# Pop-Up_5_1.net
KiCad netlist of a schematic drawn in EAGLE
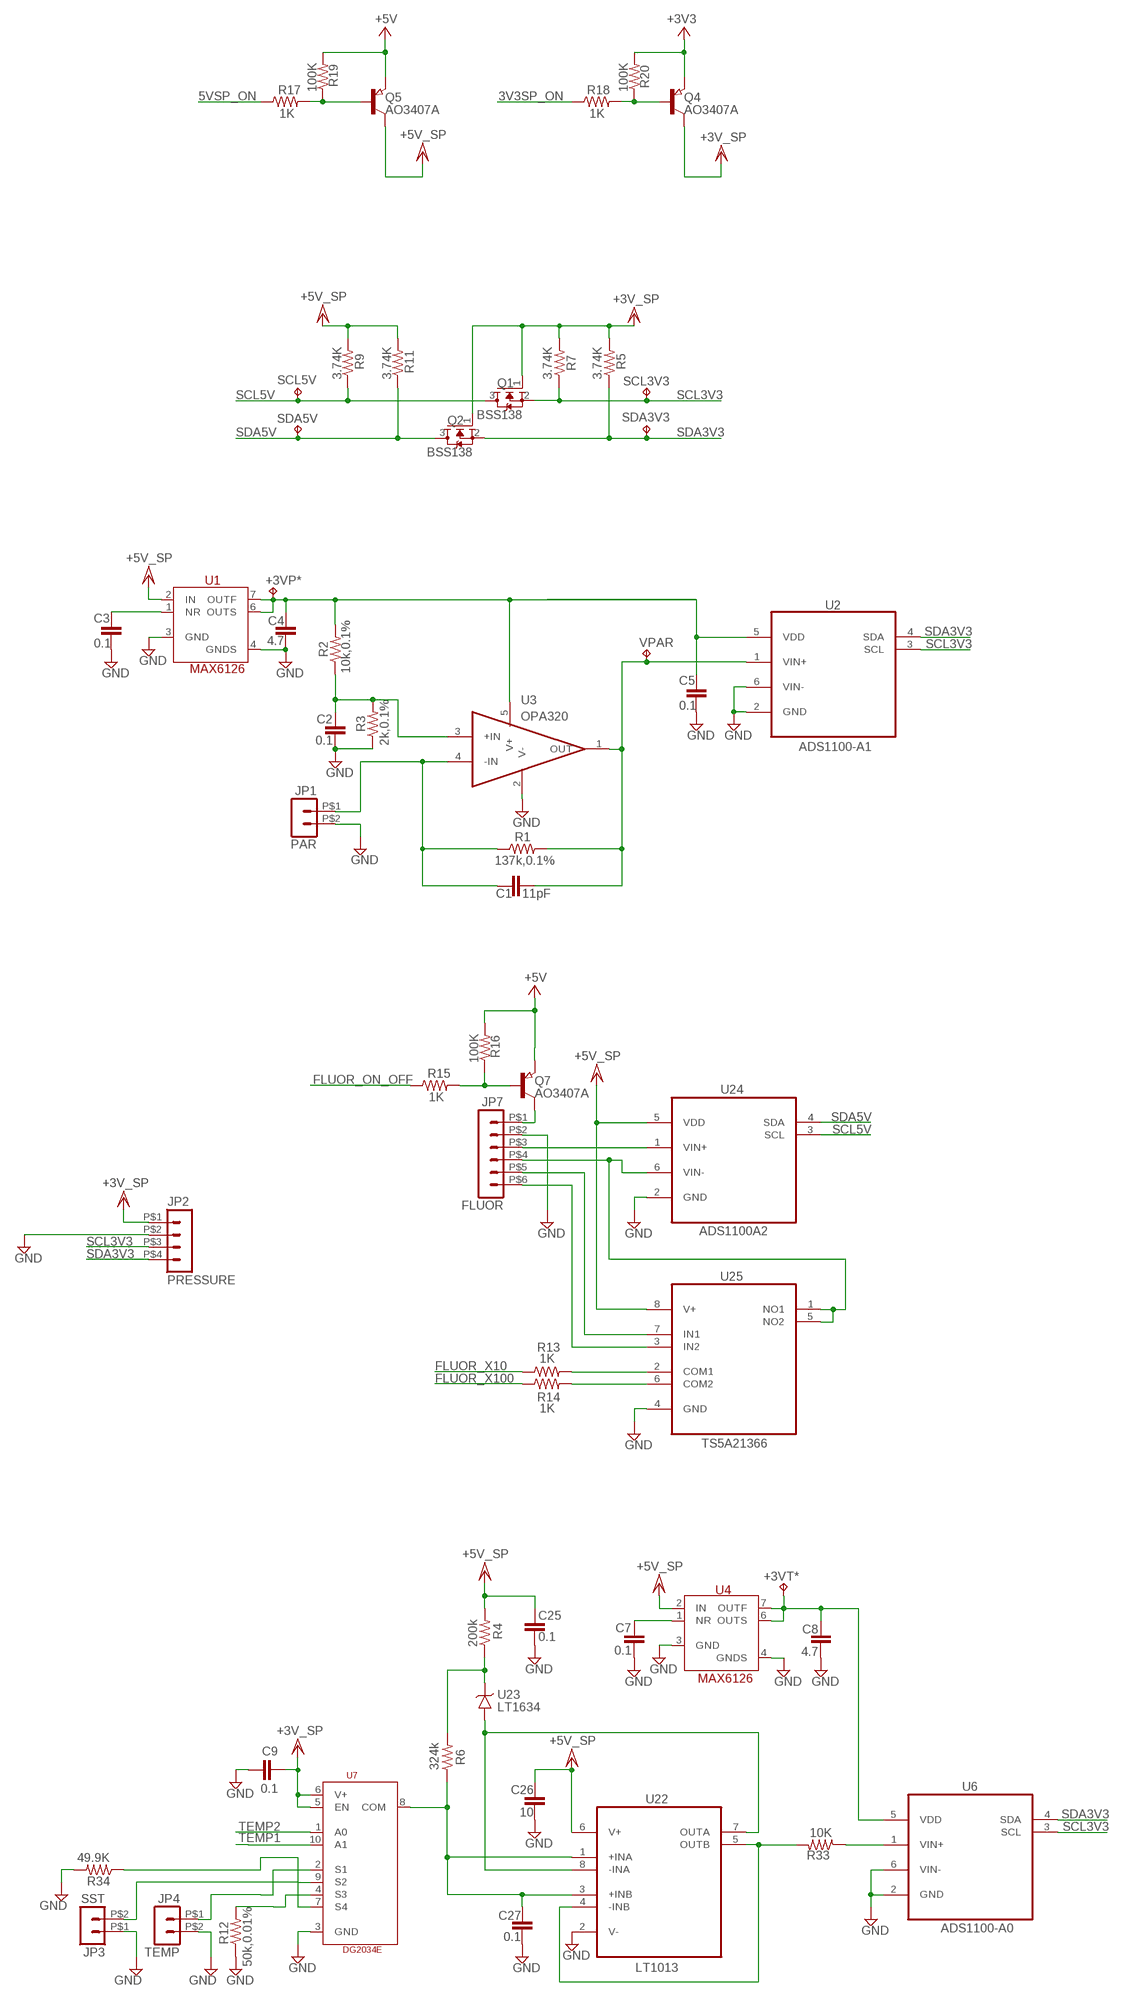
[diagram p0: schematic, sheet 1, part 1 of 2]
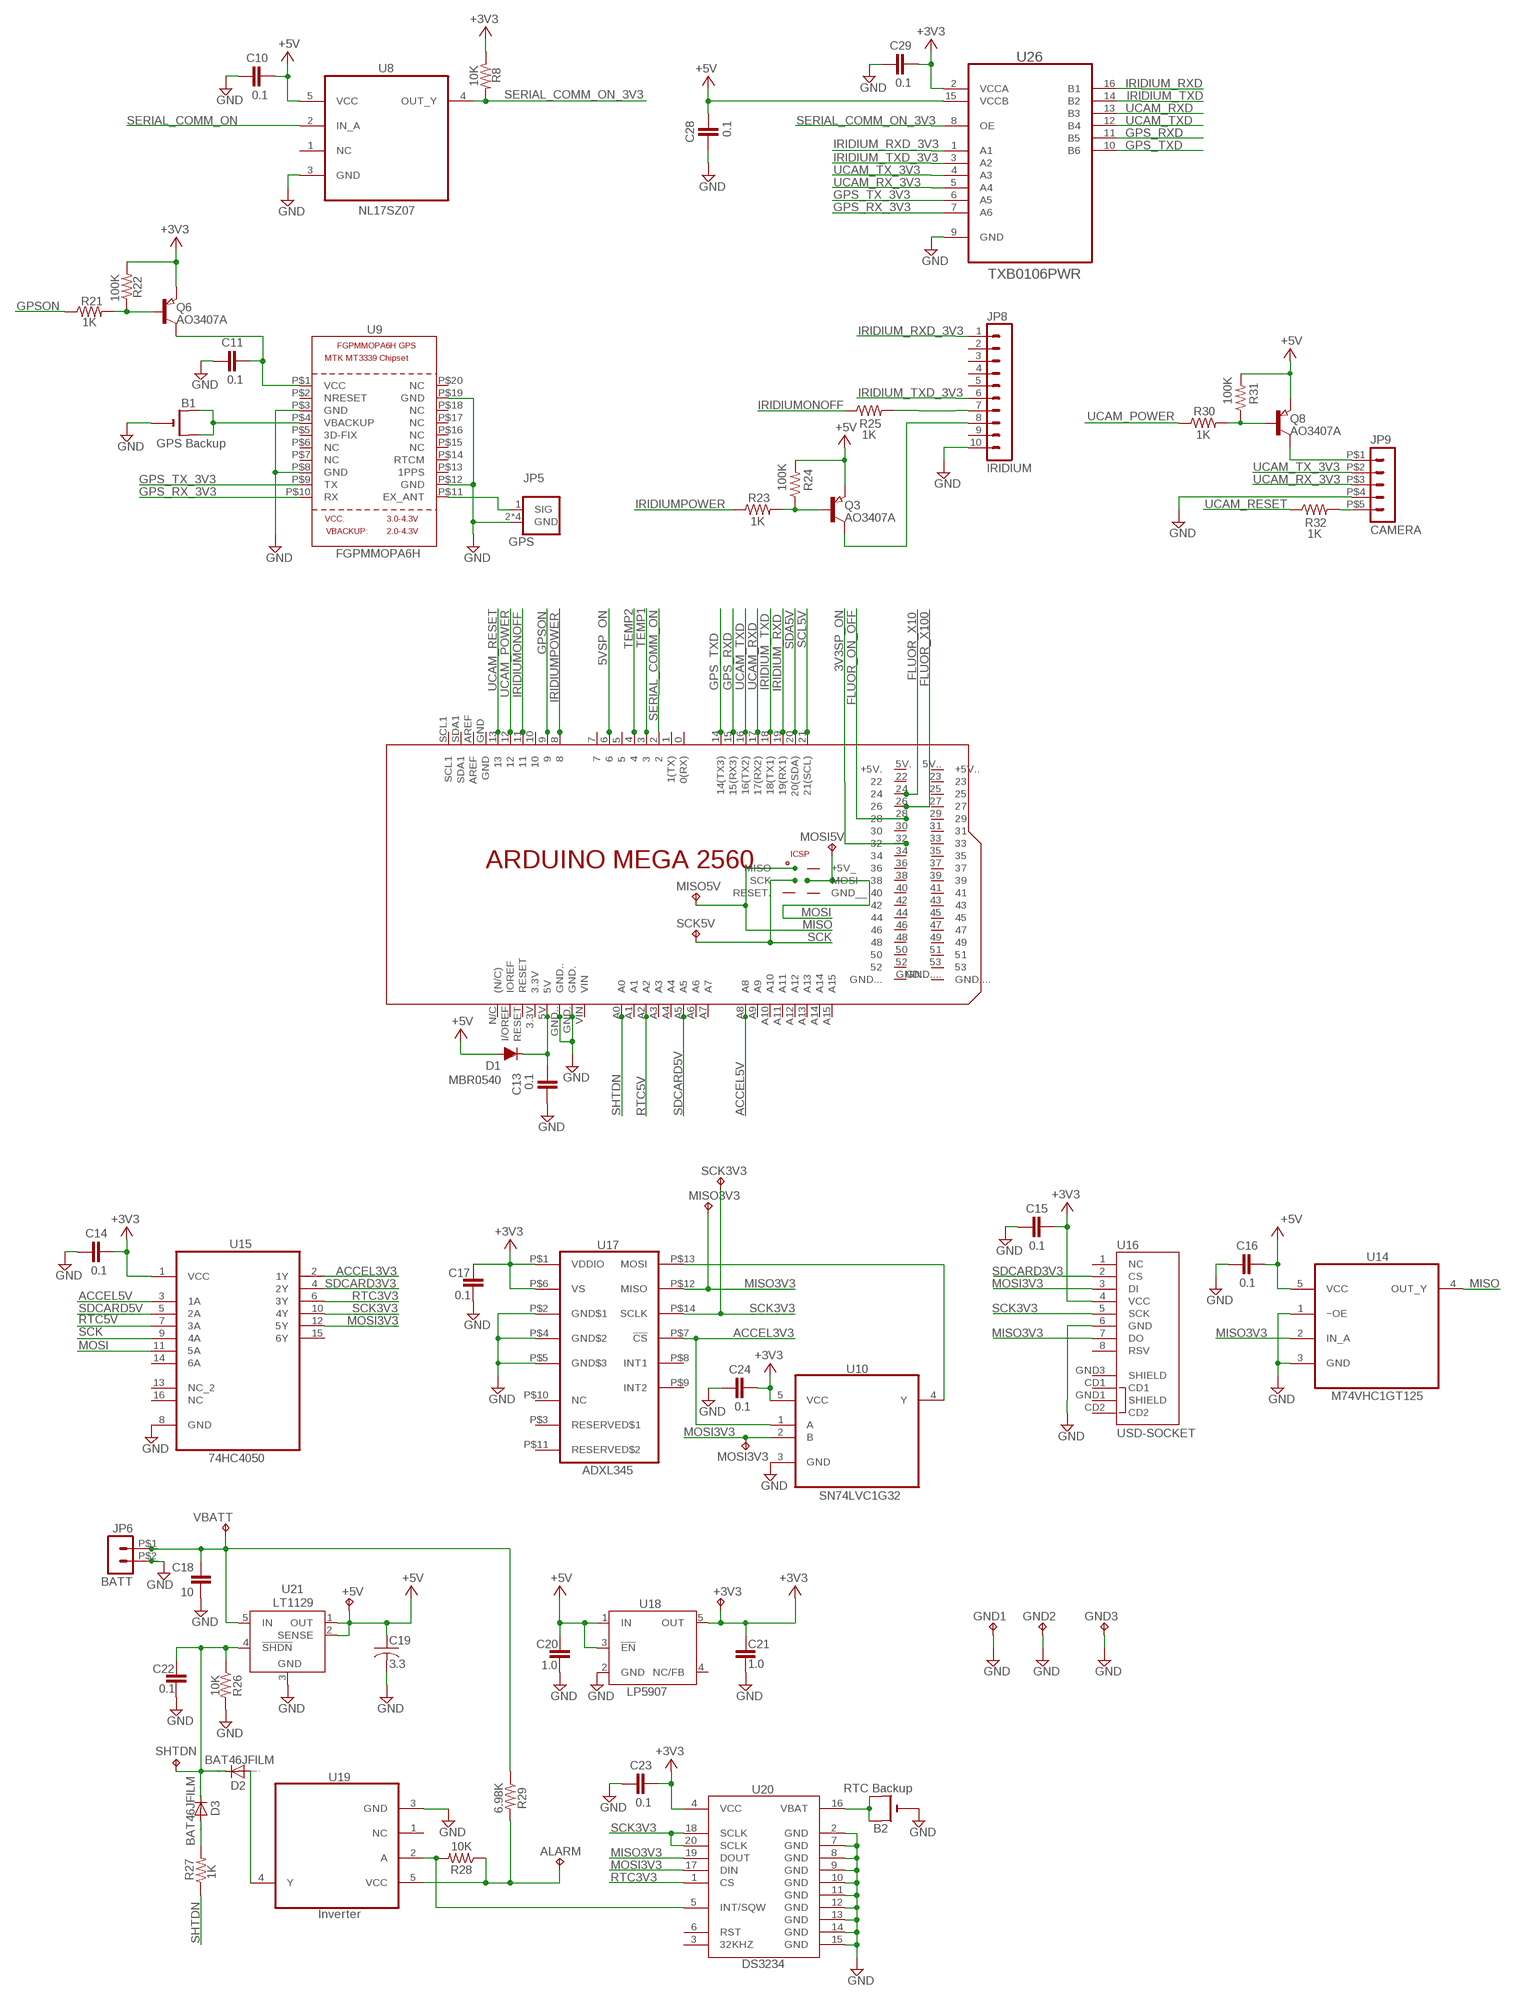
[diagram p1: schematic, sheet 1, part 2 of 2]

(export (version "E")
  (design (tool "Eeschema 10.0.6"))
  (components
    (comp (ref "+3V3")
      (value "TP-040")
      (footprint "eagle-import:TP-040")
      (libsource (lib "eagle-import") (part "TP-040"))
    )
    (comp (ref "+3VP*")
      (value "TP-040")
      (footprint "eagle-import:TP-040")
      (libsource (lib "eagle-import") (part "TP-040"))
    )
    (comp (ref "+3VT*")
      (value "TP-040")
      (footprint "eagle-import:TP-040")
      (libsource (lib "eagle-import") (part "TP-040"))
    )
    (comp (ref "+5V")
      (value "TP-040")
      (footprint "eagle-import:TP-040")
      (libsource (lib "eagle-import") (part "TP-040"))
    )
    (comp (ref "ALARM")
      (value "TP-040")
      (footprint "eagle-import:TP-040")
      (libsource (lib "eagle-import") (part "TP-040"))
    )
    (comp (ref "B1")
      (value "GPS Backup")
      (footprint "eagle-import:CR1220-SMD")
      (libsource (lib "eagle-import") (part "CR1220SMT"))
    )
    (comp (ref "B2")
      (value "RTC Backup")
      (footprint "eagle-import:CR1220-SMD")
      (libsource (lib "eagle-import") (part "CR1220SMT"))
    )
    (comp (ref "C1")
      (value "11pF")
      (footprint "eagle-import:0603-CAP")
      (fields (field (name "MPN") "2222 370 21104"))
      (libsource (lib "eagle-import") (part "CAP0603-CAP"))
    )
    (comp (ref "C2")
      (value "0.1")
      (footprint "eagle-import:0603-CAP")
      (fields (field (name "MPN") "2222 370 21104"))
      (libsource (lib "eagle-import") (part "CAP0603-CAP"))
    )
    (comp (ref "C3")
      (value "0.1")
      (footprint "eagle-import:0603-CAP")
      (fields (field (name "MPN") "2222 370 21104"))
      (libsource (lib "eagle-import") (part "CAP0603-CAP"))
    )
    (comp (ref "C4")
      (value "4.7")
      (footprint "eagle-import:0603-CAP")
      (fields (field (name "MPN") "2222 370 21104"))
      (libsource (lib "eagle-import") (part "CAP0603-CAP"))
    )
    (comp (ref "C5")
      (value "0.1")
      (footprint "eagle-import:0603-CAP")
      (fields (field (name "MPN") "2222 370 21104"))
      (libsource (lib "eagle-import") (part "CAP0603-CAP"))
    )
    (comp (ref "C7")
      (value "0.1")
      (footprint "eagle-import:0603-CAP")
      (fields (field (name "MPN") "2222 370 21104"))
      (libsource (lib "eagle-import") (part "CAP0603-CAP"))
    )
    (comp (ref "C8")
      (value "4.7")
      (footprint "eagle-import:0603-CAP")
      (fields (field (name "MPN") "2222 370 21104"))
      (libsource (lib "eagle-import") (part "CAP0603-CAP"))
    )
    (comp (ref "C9")
      (value "0.1")
      (footprint "eagle-import:0603-CAP")
      (fields (field (name "MPN") "2222 370 21104"))
      (libsource (lib "eagle-import") (part "CAP0603-CAP"))
    )
    (comp (ref "C10")
      (value "0.1")
      (footprint "eagle-import:0603-CAP")
      (fields (field (name "MPN") "2222 370 21104"))
      (libsource (lib "eagle-import") (part "CAP0603-CAP"))
    )
    (comp (ref "C11")
      (value "0.1")
      (footprint "eagle-import:0603-CAP")
      (fields (field (name "MPN") "2222 370 21104"))
      (libsource (lib "eagle-import") (part "CAP0603-CAP"))
    )
    (comp (ref "C13")
      (value "0.1")
      (footprint "eagle-import:0603-CAP")
      (fields (field (name "MPN") "2222 370 21104"))
      (libsource (lib "eagle-import") (part "CAP0603-CAP"))
    )
    (comp (ref "C14")
      (value "0.1")
      (footprint "eagle-import:0603-CAP")
      (fields (field (name "MPN") "2222 370 21104"))
      (libsource (lib "eagle-import") (part "CAP0603-CAP"))
    )
    (comp (ref "C15")
      (value "0.1")
      (footprint "eagle-import:0603-CAP")
      (fields (field (name "MPN") "2222 370 21104"))
      (libsource (lib "eagle-import") (part "CAP0603-CAP"))
    )
    (comp (ref "C16")
      (value "0.1")
      (footprint "eagle-import:0603-CAP")
      (fields (field (name "MPN") "2222 370 21104"))
      (libsource (lib "eagle-import") (part "CAP0603-CAP"))
    )
    (comp (ref "C17")
      (value "0.1")
      (footprint "eagle-import:0603-CAP")
      (fields (field (name "MPN") "2222 370 21104"))
      (libsource (lib "eagle-import") (part "CAP0603-CAP"))
    )
    (comp (ref "C18")
      (value "10")
      (footprint "eagle-import:C1206")
      (libsource (lib "eagle-import") (part "C-EUC1206"))
    )
    (comp (ref "C19")
      (value "3.3")
      (footprint "eagle-import:C1206")
      (libsource (lib "eagle-import") (part "C-USC1206"))
    )
    (comp (ref "C20")
      (value "1.0")
      (footprint "eagle-import:0603-CAP")
      (fields (field (name "MPN") "2222 370 21104"))
      (libsource (lib "eagle-import") (part "CAP0603-CAP"))
    )
    (comp (ref "C21")
      (value "1.0")
      (footprint "eagle-import:0603-CAP")
      (fields (field (name "MPN") "2222 370 21104"))
      (libsource (lib "eagle-import") (part "CAP0603-CAP"))
    )
    (comp (ref "C22")
      (value "0.1")
      (footprint "eagle-import:0603-CAP")
      (fields (field (name "MPN") "2222 370 21104"))
      (libsource (lib "eagle-import") (part "CAP0603-CAP"))
    )
    (comp (ref "C23")
      (value "0.1")
      (footprint "eagle-import:0603-CAP")
      (fields (field (name "MPN") "2222 370 21104"))
      (libsource (lib "eagle-import") (part "CAP0603-CAP"))
    )
    (comp (ref "C24")
      (value "0.1")
      (footprint "eagle-import:0603-CAP")
      (fields (field (name "MPN") "2222 370 21104"))
      (libsource (lib "eagle-import") (part "CAP0603-CAP"))
    )
    (comp (ref "C25")
      (value "0.1")
      (footprint "eagle-import:0603-CAP")
      (fields (field (name "MPN") "2222 370 21104"))
      (libsource (lib "eagle-import") (part "CAP0603-CAP"))
    )
    (comp (ref "C26")
      (value "10")
      (footprint "eagle-import:C1206")
      (fields (field (name "MPN") "2222 370 21104"))
      (libsource (lib "eagle-import") (part "C-EUC1206"))
    )
    (comp (ref "C27")
      (value "0.1")
      (footprint "eagle-import:0603-CAP")
      (fields (field (name "MPN") "2222 370 21104"))
      (libsource (lib "eagle-import") (part "CAP0603-CAP"))
    )
    (comp (ref "C28")
      (value "0.1")
      (footprint "eagle-import:0603-CAP")
      (fields (field (name "MPN") "2222 370 21104"))
      (libsource (lib "eagle-import") (part "CAP0603-CAP"))
    )
    (comp (ref "C29")
      (value "0.1")
      (footprint "eagle-import:0603-CAP")
      (fields (field (name "MPN") "2222 370 21104"))
      (libsource (lib "eagle-import") (part "CAP0603-CAP"))
    )
    (comp (ref "D1")
      (value "MBR0540")
      (footprint "eagle-import:SOD123")
      (libsource (lib "eagle-import") (part "D-FILL-SOD123"))
    )
    (comp (ref "D2")
      (value "BAT46JFILM")
      (footprint "eagle-import:SOD323-R")
      (libsource (lib "eagle-import") (part "DIODE-SOD323-R"))
    )
    (comp (ref "D3")
      (value "BAT46JFILM")
      (footprint "eagle-import:SOD323-R")
      (libsource (lib "eagle-import") (part "DIODE-SOD323-R"))
    )
    (comp (ref "GND1")
      (value "TP-040")
      (footprint "eagle-import:TP-040")
      (libsource (lib "eagle-import") (part "TP-040"))
    )
    (comp (ref "GND2")
      (value "TP-040")
      (footprint "eagle-import:TP-040")
      (libsource (lib "eagle-import") (part "TP-040"))
    )
    (comp (ref "GND3")
      (value "TP-040")
      (footprint "eagle-import:TP-040")
      (libsource (lib "eagle-import") (part "TP-040"))
    )
    (comp (ref "JP1")
      (value "PAR")
      (footprint "eagle-import:43650-0215")
      (libsource (lib "eagle-import") (part "HEADER_POS2_?43650-0215"))
    )
    (comp (ref "JP2")
      (value "PRESSURE")
      (footprint "eagle-import:43650-0415")
      (libsource (lib "eagle-import") (part "HEADER_POS4_?43650-0415"))
    )
    (comp (ref "JP3")
      (value "SST")
      (footprint "eagle-import:43650-0215")
      (libsource (lib "eagle-import") (part "HEADER_POS2_?43650-0215"))
    )
    (comp (ref "JP4")
      (value "TEMP")
      (footprint "eagle-import:43650-0215")
      (libsource (lib "eagle-import") (part "HEADER_POS2_?43650-0215"))
    )
    (comp (ref "JP5")
      (value "GPS")
      (footprint "eagle-import:AMPHENOL_901-9895-RFX")
      (fields (field (name "MPN") "901-9895-RFX"))
      (libsource (lib "eagle-import") (part "901-9895-RFX"))
    )
    (comp (ref "JP6")
      (value "BATT")
      (footprint "eagle-import:43650-0215")
      (libsource (lib "eagle-import") (part "HEADER_POS2_?43650-0215"))
    )
    (comp (ref "JP7")
      (value "FLUOR")
      (footprint "eagle-import:43045-0612")
      (libsource (lib "eagle-import") (part "HEADER_POS6_?43045-0612"))
    )
    (comp (ref "JP8")
      (value "IRIDIUM")
      (footprint "eagle-import:53398-1010")
      (libsource (lib "eagle-import") (part "53398-1010"))
    )
    (comp (ref "JP9")
      (value "CAMERA")
      (footprint "eagle-import:43650-0515")
      (libsource (lib "eagle-import") (part "HEADER_POS5_?43650-0515"))
    )
    (comp (ref "MISO3V3")
      (value "TP-040")
      (footprint "eagle-import:TP-040")
      (libsource (lib "eagle-import") (part "TP-040"))
    )
    (comp (ref "MISO5V")
      (value "TP-040")
      (footprint "eagle-import:TP-040")
      (libsource (lib "eagle-import") (part "TP-040"))
    )
    (comp (ref "MOSI3V3")
      (value "TP-040")
      (footprint "eagle-import:TP-040")
      (libsource (lib "eagle-import") (part "TP-040"))
    )
    (comp (ref "MOSI5V")
      (value "TP-040")
      (footprint "eagle-import:TP-040")
      (libsource (lib "eagle-import") (part "TP-040"))
    )
    (comp (ref "Q1")
      (value "BSS138")
      (footprint "eagle-import:SOT23")
      (libsource (lib "eagle-import") (part "MOSFET-NREFLOW"))
    )
    (comp (ref "Q2")
      (value "BSS138")
      (footprint "eagle-import:SOT23")
      (libsource (lib "eagle-import") (part "MOSFET-NREFLOW"))
    )
    (comp (ref "Q3")
      (value "AO3407A")
      (footprint "eagle-import:SOT23")
      (libsource (lib "eagle-import") (part "PNP-TRANSISTOR_SOT23"))
    )
    (comp (ref "Q4")
      (value "AO3407A")
      (footprint "eagle-import:SOT23")
      (libsource (lib "eagle-import") (part "PNP-TRANSISTOR_SOT23"))
    )
    (comp (ref "Q5")
      (value "AO3407A")
      (footprint "eagle-import:SOT23")
      (libsource (lib "eagle-import") (part "PNP-TRANSISTOR_SOT23"))
    )
    (comp (ref "Q6")
      (value "AO3407A")
      (footprint "eagle-import:SOT23")
      (libsource (lib "eagle-import") (part "PNP-TRANSISTOR_SOT23"))
    )
    (comp (ref "Q7")
      (value "AO3407A")
      (footprint "eagle-import:SOT23")
      (libsource (lib "eagle-import") (part "PNP-TRANSISTOR_SOT23"))
    )
    (comp (ref "Q8")
      (value "AO3407A")
      (footprint "eagle-import:SOT23")
      (libsource (lib "eagle-import") (part "PNP-TRANSISTOR_SOT23"))
    )
    (comp (ref "R1")
      (value "137k,0.1%")
      (footprint "eagle-import:R0603")
      (libsource (lib "eagle-import") (part "R-US_R0603"))
    )
    (comp (ref "R2")
      (value "10k,0.1%")
      (footprint "eagle-import:R0603")
      (libsource (lib "eagle-import") (part "R-US_R0603"))
    )
    (comp (ref "R3")
      (value "2k,0.1%")
      (footprint "eagle-import:R0603")
      (libsource (lib "eagle-import") (part "R-US_R0603"))
    )
    (comp (ref "R4")
      (value "200k")
      (footprint "eagle-import:R1206")
      (libsource (lib "eagle-import") (part "R-US_R1206"))
    )
    (comp (ref "R5")
      (value "3.74K")
      (footprint "eagle-import:R0603")
      (libsource (lib "eagle-import") (part "R-US_R0603"))
    )
    (comp (ref "R6")
      (value "324k")
      (footprint "eagle-import:R1206")
      (libsource (lib "eagle-import") (part "R-US_R1206"))
    )
    (comp (ref "R7")
      (value "3.74K")
      (footprint "eagle-import:R0603")
      (libsource (lib "eagle-import") (part "R-US_R0603"))
    )
    (comp (ref "R8")
      (value "10K")
      (footprint "eagle-import:R0603")
      (libsource (lib "eagle-import") (part "R-US_R0603"))
    )
    (comp (ref "R9")
      (value "3.74K")
      (footprint "eagle-import:R0603")
      (libsource (lib "eagle-import") (part "R-US_R0603"))
    )
    (comp (ref "R11")
      (value "3.74K")
      (footprint "eagle-import:R0603")
      (libsource (lib "eagle-import") (part "R-US_R0603"))
    )
    (comp (ref "R12")
      (value "50k,0.01%")
      (footprint "eagle-import:R2010")
      (libsource (lib "eagle-import") (part "R-US_R2010"))
    )
    (comp (ref "R13")
      (value "1K")
      (footprint "eagle-import:R0603")
      (libsource (lib "eagle-import") (part "R-US_R0603"))
    )
    (comp (ref "R14")
      (value "1K")
      (footprint "eagle-import:R0603")
      (libsource (lib "eagle-import") (part "R-US_R0603"))
    )
    (comp (ref "R15")
      (value "1K")
      (footprint "eagle-import:R0603")
      (libsource (lib "eagle-import") (part "R-US_R0603"))
    )
    (comp (ref "R16")
      (value "100K")
      (footprint "eagle-import:R0603")
      (libsource (lib "eagle-import") (part "R-US_R0603"))
    )
    (comp (ref "R17")
      (value "1K")
      (footprint "eagle-import:R0603")
      (libsource (lib "eagle-import") (part "R-US_R0603"))
    )
    (comp (ref "R18")
      (value "1K")
      (footprint "eagle-import:R0603")
      (libsource (lib "eagle-import") (part "R-US_R0603"))
    )
    (comp (ref "R19")
      (value "100K")
      (footprint "eagle-import:R0603")
      (libsource (lib "eagle-import") (part "R-US_R0603"))
    )
    (comp (ref "R20")
      (value "100K")
      (footprint "eagle-import:R0603")
      (libsource (lib "eagle-import") (part "R-US_R0603"))
    )
    (comp (ref "R21")
      (value "1K")
      (footprint "eagle-import:R0603")
      (libsource (lib "eagle-import") (part "R-US_R0603"))
    )
    (comp (ref "R22")
      (value "100K")
      (footprint "eagle-import:R0603")
      (libsource (lib "eagle-import") (part "R-US_R0603"))
    )
    (comp (ref "R23")
      (value "1K")
      (footprint "eagle-import:R0603")
      (libsource (lib "eagle-import") (part "R-US_R0603"))
    )
    (comp (ref "R24")
      (value "100K")
      (footprint "eagle-import:R0603")
      (libsource (lib "eagle-import") (part "R-US_R0603"))
    )
    (comp (ref "R25")
      (value "1K")
      (footprint "eagle-import:R0603")
      (libsource (lib "eagle-import") (part "R-US_R0603"))
    )
    (comp (ref "R26")
      (value "10K")
      (footprint "eagle-import:R0603")
      (libsource (lib "eagle-import") (part "R-US_R0603"))
    )
    (comp (ref "R27")
      (value "1K")
      (footprint "eagle-import:R0603")
      (libsource (lib "eagle-import") (part "R-US_R0603"))
    )
    (comp (ref "R28")
      (value "10K")
      (footprint "eagle-import:R0603")
      (libsource (lib "eagle-import") (part "R-US_R0603"))
    )
    (comp (ref "R29")
      (value "6.98K")
      (footprint "eagle-import:R0603")
      (libsource (lib "eagle-import") (part "R-US_R0603"))
    )
    (comp (ref "R30")
      (value "1K")
      (footprint "eagle-import:R0603")
      (libsource (lib "eagle-import") (part "R-US_R0603"))
    )
    (comp (ref "R31")
      (value "100K")
      (footprint "eagle-import:R0603")
      (libsource (lib "eagle-import") (part "R-US_R0603"))
    )
    (comp (ref "R32")
      (value "1K")
      (footprint "eagle-import:R0603")
      (libsource (lib "eagle-import") (part "R-US_R0603"))
    )
    (comp (ref "R33")
      (value "10K")
      (footprint "eagle-import:R0603")
      (libsource (lib "eagle-import") (part "R-US_R0603"))
    )
    (comp (ref "R34")
      (value "49.9K")
      (footprint "eagle-import:R0603")
      (libsource (lib "eagle-import") (part "R-US_R0603"))
    )
    (comp (ref "SCK3V3")
      (value "TP-040")
      (footprint "eagle-import:TP-040")
      (libsource (lib "eagle-import") (part "TP-040"))
    )
    (comp (ref "SCK5V")
      (value "TP-040")
      (footprint "eagle-import:TP-040")
      (libsource (lib "eagle-import") (part "TP-040"))
    )
    (comp (ref "SCL3V3")
      (value "TP-040")
      (footprint "eagle-import:TP-040")
      (libsource (lib "eagle-import") (part "TP-040"))
    )
    (comp (ref "SCL5V")
      (value "TP-040")
      (footprint "eagle-import:TP-040")
      (libsource (lib "eagle-import") (part "TP-040"))
    )
    (comp (ref "SDA3V3")
      (value "TP-040")
      (footprint "eagle-import:TP-040")
      (libsource (lib "eagle-import") (part "TP-040"))
    )
    (comp (ref "SDA5V")
      (value "TP-040")
      (footprint "eagle-import:TP-040")
      (libsource (lib "eagle-import") (part "TP-040"))
    )
    (comp (ref "SHTDN")
      (value "TP-040")
      (footprint "eagle-import:TP-040")
      (libsource (lib "eagle-import") (part "TP-040"))
    )
    (comp (ref "U1")
      (value "MAX6126")
      (footprint "eagle-import:SOIC127P600X175-8N")
      (libsource (lib "eagle-import") (part "MAX6126"))
    )
    (comp (ref "U2")
      (value "ADS1100-A1")
      (footprint "eagle-import:SOT95P280X145-6N")
      (fields (field (name "MPN") "ADS1100A0IDBVT"))
      (libsource (lib "eagle-import") (part "ADS1100A0IDBVT"))
    )
    (comp (ref "U3")
      (value "OPA320")
      (footprint "eagle-import:SOT95P280X145-5N")
      (fields (field (name "MPN") "OPA320AIDBVT"))
      (libsource (lib "eagle-import") (part "OPA320AIDBVT"))
    )
    (comp (ref "U4")
      (value "MAX6126")
      (footprint "eagle-import:SOIC127P600X175-8N")
      (libsource (lib "eagle-import") (part "MAX6126"))
    )
    (comp (ref "U6")
      (value "ADS1100-A0")
      (footprint "eagle-import:SOT95P280X145-6N")
      (fields (field (name "MPN") "ADS1100A0IDBVT"))
      (libsource (lib "eagle-import") (part "ADS1100A0IDBVT"))
    )
    (comp (ref "U7")
      (value "DG2034E")
      (footprint "eagle-import:MSOP10")
      (libsource (lib "eagle-import") (part "DG2034E"))
    )
    (comp (ref "U8")
      (value "NL17SZ07")
      (footprint "eagle-import:SOT65P210X110-5N")
      (fields (field (name "MPN") "NL17SZ07DFT2G"))
      (libsource (lib "eagle-import") (part "NL17SZ07DFT2G"))
    )
    (comp (ref "U9")
      (value "FGPMMOPA6H")
      (footprint "eagle-import:FGPMMOPA6H")
      (libsource (lib "eagle-import") (part "GPS_FGPMMOPA6H"))
    )
    (comp (ref "U10")
      (value "SN74LVC1G32")
      (footprint "eagle-import:SOT65P210X110-5N")
      (fields (field (name "MPN") "SN74LVC1G32DCKT"))
      (libsource (lib "eagle-import") (part "SN74LVC1G32DCKT"))
    )
    (comp (ref "U12")
      (value "Arduino MEGA2650")
      (footprint "eagle-import:MEGA2650_UPSIDEDOWNMOUNT")
      (libsource (lib "eagle-import") (part "MEGA2650_UPSIDEDOWNMOUNT"))
    )
    (comp (ref "U14")
      (value "M74VHC1GT125")
      (footprint "eagle-import:SOT65P210X110-5N")
      (fields (field (name "MPN") "M74VHC1GT125DF1G"))
      (libsource (lib "eagle-import") (part "M74VHC1GT125DF1G"))
    )
    (comp (ref "U15")
      (value "74HC4050")
      (footprint "eagle-import:SOIC127P600X175-16N")
      (fields (field (name "MPN") "M74HC4050RM13TR"))
      (libsource (lib "eagle-import") (part "M74HC4050RM13TR"))
    )
    (comp (ref "U16")
      (value "USD-SOCKET")
      (footprint "eagle-import:MICROSD_1_1")
      (libsource (lib "eagle-import") (part "USD-SOCKET"))
    )
    (comp (ref "U17")
      (value "ADXL345")
      (footprint "eagle-import:LGA14")
      (libsource (lib "eagle-import") (part "ADXL345"))
    )
    (comp (ref "U18")
      (value "LP5907")
      (footprint "eagle-import:SOT23-DBV")
      (fields (field (name "MF") "TEXAS INSTRUMENTS") (field (name "MPN") "TPS77033DBVT"))
      (libsource (lib "eagle-import") (part "TPS77033"))
    )
    (comp (ref "U19")
      (value "Inverter")
      (footprint "eagle-import:SOT95P280X145-5N")
      (fields (field (name "MPN") "1P1G14MDBVREPG4") (field (name "OC_NEWARK") "unknown"))
      (libsource (lib "eagle-import") (part "1P1G14MDBVREPG4"))
    )
    (comp (ref "U20")
      (value "DS3234")
      (footprint "eagle-import:DS3234")
      (libsource (lib "eagle-import") (part "DS3234"))
    )
    (comp (ref "U21")
      (value "LT1129")
      (footprint "eagle-import:Q5-DD")
      (fields (field (name "MPN") "LT1129CQ-5#PBF"))
      (libsource (lib "eagle-import") (part "LT1129CQ-5"))
    )
    (comp (ref "U22")
      (value "LT1013")
      (footprint "eagle-import:SOIC127P600X175-8N")
      (fields (field (name "MPN") "LT1013IS8#PBF"))
      (libsource (lib "eagle-import") (part "LT1013IS8PBF"))
    )
    (comp (ref "U23")
      (value "LT1634")
      (footprint "eagle-import:S8")
      (libsource (lib "eagle-import") (part "LT1634BIS8-1.25"))
    )
    (comp (ref "U24")
      (value "ADS1100A2")
      (footprint "eagle-import:SOT95P280X145-6N")
      (fields (field (name "MPN") "ADS1100A2IDBVT"))
      (libsource (lib "eagle-import") (part "ADS1100A2IDBVT"))
    )
    (comp (ref "U25")
      (value "TS5A21366")
      (footprint "eagle-import:SOP50P310X90-8N")
      (fields (field (name "MPN") "TS5A21366DCUR"))
      (libsource (lib "eagle-import") (part "TS5A21366DCUR"))
    )
    (comp (ref "U26")
      (value "TXB0106PWR")
      (footprint "eagle-import:SOP65P640X120-16N")
      (libsource (lib "eagle-import") (part "TXB0106PWR"))
    )
    (comp (ref "VBATT")
      (value "TP-040")
      (footprint "eagle-import:TP-040")
      (libsource (lib "eagle-import") (part "TP-040"))
    )
    (comp (ref "VPAR")
      (value "TP-040")
      (footprint "eagle-import:TP-040")
      (libsource (lib "eagle-import") (part "TP-040"))
    )
  )
  (nets
    (net (code "1") (name "+3V3") (class "Default")
      (node (ref "+3V3") (pin "1") (pinfunction "1_1") (pintype "passive"))
      (node (ref "C14") (pin "1") (pinfunction "1_1") (pintype "passive"))
      (node (ref "C15") (pin "1") (pinfunction "1_1") (pintype "passive"))
      (node (ref "C17") (pin "1") (pinfunction "1_1") (pintype "passive"))
      (node (ref "C21") (pin "1") (pinfunction "1_1") (pintype "passive"))
      (node (ref "C23") (pin "1") (pinfunction "1_1") (pintype "passive"))
      (node (ref "C24") (pin "1") (pinfunction "1_1") (pintype "passive"))
      (node (ref "C29") (pin "1") (pinfunction "1_1") (pintype "passive"))
      (node (ref "Q4") (pin "2") (pinfunction "E_2") (pintype "passive"))
      (node (ref "Q6") (pin "2") (pinfunction "E_2") (pintype "passive"))
      (node (ref "R20") (pin "2") (pinfunction "2_2") (pintype "passive"))
      (node (ref "R22") (pin "2") (pinfunction "2_2") (pintype "passive"))
      (node (ref "R8") (pin "1") (pinfunction "1_1") (pintype "passive"))
      (node (ref "U10") (pin "5") (pinfunction "VCC_5") (pintype "power_in"))
      (node (ref "U15") (pin "1") (pinfunction "VCC_1") (pintype "power_in"))
      (node (ref "U16") (pin "4") (pinfunction "VCC_4") (pintype "bidirectional"))
      (node (ref "U17") (pin "P$1") (pinfunction "VDDIO_P$1") (pintype "power_in"))
      (node (ref "U17") (pin "P$6") (pinfunction "VS_P$6") (pintype "power_in"))
      (node (ref "U18") (pin "5") (pinfunction "OUT_5") (pintype "passive"))
      (node (ref "U20") (pin "4") (pinfunction "VCC_4") (pintype "bidirectional"))
      (node (ref "U26") (pin "2") (pinfunction "VCCA_2") (pintype "power_in"))
    )
    (net (code "2") (name "+3V_SP") (class "Default")
      (node (ref "C9") (pin "1") (pinfunction "1_1") (pintype "passive"))
      (node (ref "JP2") (pin "P$1") (pinfunction "1_P$1") (pintype "passive"))
      (node (ref "Q1") (pin "1") (pinfunction "G_1") (pintype "bidirectional"))
      (node (ref "Q2") (pin "1") (pinfunction "G_1") (pintype "bidirectional"))
      (node (ref "Q4") (pin "3") (pinfunction "C_3") (pintype "passive"))
      (node (ref "R5") (pin "2") (pinfunction "2_2") (pintype "passive"))
      (node (ref "R7") (pin "2") (pinfunction "2_2") (pintype "passive"))
      (node (ref "U7") (pin "5") (pinfunction "EN_5") (pintype "bidirectional"))
      (node (ref "U7") (pin "6") (pinfunction "V+_6") (pintype "bidirectional"))
    )
    (net (code "3") (name "+5V") (class "Default")
      (node (ref "+5V") (pin "1") (pinfunction "1_1") (pintype "passive"))
      (node (ref "C10") (pin "1") (pinfunction "1_1") (pintype "passive"))
      (node (ref "C16") (pin "1") (pinfunction "1_1") (pintype "passive"))
      (node (ref "C19") (pin "1") (pinfunction "1_1") (pintype "passive"))
      (node (ref "C20") (pin "1") (pinfunction "1_1") (pintype "passive"))
      (node (ref "C28") (pin "1") (pinfunction "1_1") (pintype "passive"))
      (node (ref "D1") (pin "2") (pinfunction "A_2") (pintype "passive"))
      (node (ref "Q3") (pin "2") (pinfunction "E_2") (pintype "passive"))
      (node (ref "Q5") (pin "2") (pinfunction "E_2") (pintype "passive"))
      (node (ref "Q7") (pin "2") (pinfunction "E_2") (pintype "passive"))
      (node (ref "Q8") (pin "2") (pinfunction "E_2") (pintype "passive"))
      (node (ref "R16") (pin "2") (pinfunction "2_2") (pintype "passive"))
      (node (ref "R19") (pin "2") (pinfunction "2_2") (pintype "passive"))
      (node (ref "R24") (pin "2") (pinfunction "2_2") (pintype "passive"))
      (node (ref "R31") (pin "2") (pinfunction "2_2") (pintype "passive"))
      (node (ref "U14") (pin "5") (pinfunction "VCC_5") (pintype "power_in"))
      (node (ref "U18") (pin "1") (pinfunction "IN_1") (pintype "input"))
      (node (ref "U18") (pin "3") (pinfunction "~{EN}_3") (pintype "input"))
      (node (ref "U21") (pin "1") (pinfunction "OUT_1") (pintype "output"))
      (node (ref "U21") (pin "2") (pinfunction "SENSE_2") (pintype "input"))
      (node (ref "U26") (pin "15") (pinfunction "VCCB_15") (pintype "power_in"))
      (node (ref "U8") (pin "5") (pinfunction "VCC_5") (pintype "power_in"))
    )
    (net (code "4") (name "+5V_SP") (class "Default")
      (node (ref "C25") (pin "1") (pinfunction "1_1") (pintype "passive"))
      (node (ref "C26") (pin "1") (pinfunction "1_1") (pintype "passive"))
      (node (ref "Q5") (pin "3") (pinfunction "C_3") (pintype "passive"))
      (node (ref "R11") (pin "2") (pinfunction "2_2") (pintype "passive"))
      (node (ref "R4") (pin "2") (pinfunction "2_2") (pintype "passive"))
      (node (ref "R9") (pin "2") (pinfunction "2_2") (pintype "passive"))
      (node (ref "U1") (pin "2") (pinfunction "IN_2") (pintype "input"))
      (node (ref "U22") (pin "6") (pinfunction "V+_6") (pintype "power_in"))
      (node (ref "U24") (pin "5") (pinfunction "VDD_5") (pintype "power_in"))
      (node (ref "U25") (pin "8") (pinfunction "V+_8") (pintype "power_in"))
      (node (ref "U4") (pin "2") (pinfunction "IN_2") (pintype "input"))
    )
    (net (code "5") (name "/3V3SP_ON") (class "Default")
      (node (ref "R18") (pin "1") (pinfunction "1_1") (pintype "passive"))
      (node (ref "U12") (pin "32") (pinfunction "32_32") (pintype "bidirectional"))
    )
    (net (code "6") (name "/5VSP_ON") (class "Default")
      (node (ref "R17") (pin "1") (pinfunction "1_1") (pintype "passive"))
      (node (ref "U12") (pin "6") (pinfunction "6_6") (pintype "bidirectional"))
    )
    (net (code "7") (name "/ACCEL3V3") (class "Default")
      (node (ref "U10") (pin "1") (pinfunction "A_1") (pintype "input"))
      (node (ref "U15") (pin "2") (pinfunction "1Y_2") (pintype "output"))
      (node (ref "U17") (pin "P$7") (pinfunction "~{CS}_P$7") (pintype "input"))
    )
    (net (code "8") (name "/ACCEL5V") (class "Default")
      (node (ref "U12") (pin "A8") (pinfunction "A8_A8") (pintype "bidirectional"))
      (node (ref "U15") (pin "3") (pinfunction "1A_3") (pintype "input"))
    )
    (net (code "9") (name "/FLUOR_ON_OFF") (class "Default")
      (node (ref "R15") (pin "1") (pinfunction "1_1") (pintype "passive"))
      (node (ref "U12") (pin "28") (pinfunction "28_28") (pintype "bidirectional"))
    )
    (net (code "10") (name "/FLUOR_X10") (class "Default")
      (node (ref "R13") (pin "1") (pinfunction "1_1") (pintype "passive"))
      (node (ref "U12") (pin "24") (pinfunction "24_24") (pintype "bidirectional"))
    )
    (net (code "11") (name "/FLUOR_X100") (class "Default")
      (node (ref "R14") (pin "1") (pinfunction "1_1") (pintype "passive"))
      (node (ref "U12") (pin "26") (pinfunction "26_26") (pintype "bidirectional"))
    )
    (net (code "12") (name "/GPSON") (class "Default")
      (node (ref "R21") (pin "1") (pinfunction "1_1") (pintype "passive"))
      (node (ref "U12") (pin "9") (pinfunction "9_9") (pintype "bidirectional"))
    )
    (net (code "13") (name "/GPS_RXD") (class "Default")
      (node (ref "U12") (pin "15") (pinfunction "15(RX3)_15") (pintype "bidirectional"))
      (node (ref "U26") (pin "11") (pinfunction "B5_11") (pintype "bidirectional"))
    )
    (net (code "14") (name "/GPS_RX_3V3") (class "Default")
      (node (ref "U26") (pin "7") (pinfunction "A6_7") (pintype "bidirectional"))
      (node (ref "U9") (pin "P$10") (pinfunction "RX_P$10") (pintype "bidirectional"))
    )
    (net (code "15") (name "/GPS_TXD") (class "Default")
      (node (ref "U12") (pin "14") (pinfunction "14(TX3)_14") (pintype "bidirectional"))
      (node (ref "U26") (pin "10") (pinfunction "B6_10") (pintype "bidirectional"))
    )
    (net (code "16") (name "/GPS_TX_3V3") (class "Default")
      (node (ref "U26") (pin "6") (pinfunction "A5_6") (pintype "bidirectional"))
      (node (ref "U9") (pin "P$9") (pinfunction "TX_P$9") (pintype "bidirectional"))
    )
    (net (code "17") (name "/IRIDIUMONOFF") (class "Default")
      (node (ref "R25") (pin "1") (pinfunction "1_1") (pintype "passive"))
      (node (ref "U12") (pin "11") (pinfunction "11_11") (pintype "bidirectional"))
    )
    (net (code "18") (name "/IRIDIUMPOWER") (class "Default")
      (node (ref "R23") (pin "1") (pinfunction "1_1") (pintype "passive"))
      (node (ref "U12") (pin "8") (pinfunction "8_8") (pintype "bidirectional"))
    )
    (net (code "19") (name "/IRIDIUM_RXD") (class "Default")
      (node (ref "U12") (pin "19") (pinfunction "19(RX1)_19") (pintype "bidirectional"))
      (node (ref "U26") (pin "16") (pinfunction "B1_16") (pintype "bidirectional"))
    )
    (net (code "20") (name "/IRIDIUM_RXD_3V3") (class "Default")
      (node (ref "JP8") (pin "1") (pinfunction "1_1") (pintype "passive"))
      (node (ref "U26") (pin "1") (pinfunction "A1_1") (pintype "bidirectional"))
    )
    (net (code "21") (name "/IRIDIUM_TXD") (class "Default")
      (node (ref "U12") (pin "18") (pinfunction "18(TX1)_18") (pintype "bidirectional"))
      (node (ref "U26") (pin "14") (pinfunction "B2_14") (pintype "bidirectional"))
    )
    (net (code "22") (name "/IRIDIUM_TXD_3V3") (class "Default")
      (node (ref "JP8") (pin "6") (pinfunction "6_6") (pintype "passive"))
      (node (ref "U26") (pin "3") (pinfunction "A2_3") (pintype "bidirectional"))
    )
    (net (code "23") (name "/MISO") (class "Default")
      (node (ref "MISO5V") (pin "1") (pinfunction "1_1") (pintype "passive"))
      (node (ref "U12") (pin "MISO") (pinfunction "MISO_MISO") (pintype "bidirectional"))
      (node (ref "U14") (pin "4") (pinfunction "OUT_Y_4") (pintype "output"))
    )
    (net (code "24") (name "/MISO3V3") (class "Default")
      (node (ref "MISO3V3") (pin "1") (pinfunction "1_1") (pintype "passive"))
      (node (ref "U14") (pin "2") (pinfunction "IN_A_2") (pintype "input"))
      (node (ref "U16") (pin "7") (pinfunction "DO_7") (pintype "bidirectional"))
      (node (ref "U17") (pin "P$12") (pinfunction "MISO_P$12") (pintype "output"))
      (node (ref "U20") (pin "19") (pinfunction "DOUT_19") (pintype "bidirectional"))
    )
    (net (code "25") (name "/MOSI") (class "Default")
      (node (ref "MOSI5V") (pin "1") (pinfunction "1_1") (pintype "passive"))
      (node (ref "U12") (pin "MOSI") (pinfunction "MOSI_MOSI") (pintype "bidirectional"))
      (node (ref "U15") (pin "11") (pinfunction "5A_11") (pintype "input"))
    )
    (net (code "26") (name "/MOSI3V3") (class "Default")
      (node (ref "MOSI3V3") (pin "1") (pinfunction "1_1") (pintype "passive"))
      (node (ref "U10") (pin "2") (pinfunction "B_2") (pintype "input"))
      (node (ref "U15") (pin "12") (pinfunction "5Y_12") (pintype "output"))
      (node (ref "U16") (pin "3") (pinfunction "DI_3") (pintype "bidirectional"))
      (node (ref "U20") (pin "17") (pinfunction "DIN_17") (pintype "bidirectional"))
    )
    (net (code "27") (name "/RTC3V3") (class "Default")
      (node (ref "U15") (pin "6") (pinfunction "3Y_6") (pintype "output"))
      (node (ref "U20") (pin "1") (pinfunction "CS_1") (pintype "bidirectional"))
    )
    (net (code "28") (name "/RTC5V") (class "Default")
      (node (ref "U12") (pin "A2") (pinfunction "A2_A2") (pintype "bidirectional"))
      (node (ref "U15") (pin "7") (pinfunction "3A_7") (pintype "input"))
    )
    (net (code "29") (name "/SCK") (class "Default")
      (node (ref "SCK5V") (pin "1") (pinfunction "1_1") (pintype "passive"))
      (node (ref "U12") (pin "SCK") (pinfunction "SCK_SCK") (pintype "bidirectional"))
      (node (ref "U15") (pin "9") (pinfunction "4A_9") (pintype "input"))
    )
    (net (code "30") (name "/SCK3V3") (class "Default")
      (node (ref "SCK3V3") (pin "1") (pinfunction "1_1") (pintype "passive"))
      (node (ref "U15") (pin "10") (pinfunction "4Y_10") (pintype "output"))
      (node (ref "U16") (pin "5") (pinfunction "SCK_5") (pintype "bidirectional"))
      (node (ref "U17") (pin "P$14") (pinfunction "SCLK_P$14") (pintype "input"))
      (node (ref "U20") (pin "18") (pinfunction "SCLK_18") (pintype "bidirectional"))
      (node (ref "U20") (pin "20") (pinfunction "SCLK_20") (pintype "bidirectional"))
    )
    (net (code "31") (name "/SCL3V3") (class "Default")
      (node (ref "JP2") (pin "P$3") (pinfunction "3_P$3") (pintype "passive"))
      (node (ref "Q1") (pin "2") (pinfunction "S_2") (pintype "bidirectional"))
      (node (ref "R7") (pin "1") (pinfunction "1_1") (pintype "passive"))
      (node (ref "SCL3V3") (pin "1") (pinfunction "1_1") (pintype "passive"))
      (node (ref "U2") (pin "3") (pinfunction "SCL_3") (pintype "output"))
      (node (ref "U6") (pin "3") (pinfunction "SCL_3") (pintype "output"))
    )
    (net (code "32") (name "/SCL5V") (class "Default")
      (node (ref "Q1") (pin "3") (pinfunction "D_3") (pintype "bidirectional"))
      (node (ref "R9") (pin "1") (pinfunction "1_1") (pintype "passive"))
      (node (ref "SCL5V") (pin "1") (pinfunction "1_1") (pintype "passive"))
      (node (ref "U12") (pin "21") (pinfunction "21(SCL)_21") (pintype "bidirectional"))
      (node (ref "U24") (pin "3") (pinfunction "SCL_3") (pintype "output"))
    )
    (net (code "33") (name "/SDA3V3") (class "Default")
      (node (ref "JP2") (pin "P$4") (pinfunction "4_P$4") (pintype "passive"))
      (node (ref "Q2") (pin "2") (pinfunction "S_2") (pintype "bidirectional"))
      (node (ref "R5") (pin "1") (pinfunction "1_1") (pintype "passive"))
      (node (ref "SDA3V3") (pin "1") (pinfunction "1_1") (pintype "passive"))
      (node (ref "U2") (pin "4") (pinfunction "SDA_4") (pintype "output"))
      (node (ref "U6") (pin "4") (pinfunction "SDA_4") (pintype "output"))
    )
    (net (code "34") (name "/SDA5V") (class "Default")
      (node (ref "Q2") (pin "3") (pinfunction "D_3") (pintype "bidirectional"))
      (node (ref "R11") (pin "1") (pinfunction "1_1") (pintype "passive"))
      (node (ref "SDA5V") (pin "1") (pinfunction "1_1") (pintype "passive"))
      (node (ref "U12") (pin "20") (pinfunction "20(SDA)_20") (pintype "bidirectional"))
      (node (ref "U24") (pin "4") (pinfunction "SDA_4") (pintype "output"))
    )
    (net (code "35") (name "/SDCARD3V3") (class "Default")
      (node (ref "U15") (pin "4") (pinfunction "2Y_4") (pintype "output"))
      (node (ref "U16") (pin "2") (pinfunction "CS_2") (pintype "bidirectional"))
    )
    (net (code "36") (name "/SDCARD5V") (class "Default")
      (node (ref "U12") (pin "A5") (pinfunction "A5_A5") (pintype "bidirectional"))
      (node (ref "U15") (pin "5") (pinfunction "2A_5") (pintype "input"))
    )
    (net (code "37") (name "/SERIAL_COMM_ON") (class "Default")
      (node (ref "U12") (pin "2") (pinfunction "2_2") (pintype "bidirectional"))
      (node (ref "U8") (pin "2") (pinfunction "IN_A_2") (pintype "input"))
    )
    (net (code "38") (name "/SERIAL_COMM_ON_3V3") (class "Default")
      (node (ref "R8") (pin "2") (pinfunction "2_2") (pintype "passive"))
      (node (ref "U26") (pin "8") (pinfunction "OE_8") (pintype "input"))
      (node (ref "U8") (pin "4") (pinfunction "OUT_Y_4") (pintype "output"))
    )
    (net (code "39") (name "/SHTDN") (class "Default")
      (node (ref "R27") (pin "1") (pinfunction "1_1") (pintype "passive"))
      (node (ref "U12") (pin "A0") (pinfunction "A0_A0") (pintype "bidirectional"))
    )
    (net (code "40") (name "/TEMP1") (class "Default")
      (node (ref "U12") (pin "3") (pinfunction "3_3") (pintype "bidirectional"))
      (node (ref "U7") (pin "10") (pinfunction "A1_10") (pintype "bidirectional"))
    )
    (net (code "41") (name "/TEMP2") (class "Default")
      (node (ref "U12") (pin "4") (pinfunction "4_4") (pintype "bidirectional"))
      (node (ref "U7") (pin "1") (pinfunction "A0_1") (pintype "bidirectional"))
    )
    (net (code "42") (name "/UCAM_POWER") (class "Default")
      (node (ref "R30") (pin "1") (pinfunction "1_1") (pintype "passive"))
      (node (ref "U12") (pin "12") (pinfunction "12_12") (pintype "bidirectional"))
    )
    (net (code "43") (name "/UCAM_RESET") (class "Default")
      (node (ref "R32") (pin "1") (pinfunction "1_1") (pintype "passive"))
      (node (ref "U12") (pin "13") (pinfunction "13_13") (pintype "bidirectional"))
    )
    (net (code "44") (name "/UCAM_RXD") (class "Default")
      (node (ref "U12") (pin "17") (pinfunction "17(RX2)_17") (pintype "bidirectional"))
      (node (ref "U26") (pin "13") (pinfunction "B3_13") (pintype "bidirectional"))
    )
    (net (code "45") (name "/UCAM_RX_3V3") (class "Default")
      (node (ref "JP9") (pin "P$3") (pinfunction "3_P$3") (pintype "passive"))
      (node (ref "U26") (pin "5") (pinfunction "A4_5") (pintype "bidirectional"))
    )
    (net (code "46") (name "/UCAM_TXD") (class "Default")
      (node (ref "U12") (pin "16") (pinfunction "16(TX2)_16") (pintype "bidirectional"))
      (node (ref "U26") (pin "12") (pinfunction "B4_12") (pintype "bidirectional"))
    )
    (net (code "47") (name "/UCAM_TX_3V3") (class "Default")
      (node (ref "JP9") (pin "P$2") (pinfunction "2_P$2") (pintype "passive"))
      (node (ref "U26") (pin "4") (pinfunction "A3_4") (pintype "bidirectional"))
    )
    (net (code "48") (name "GND") (class "Default")
      (node (ref "B1") (pin "-") (pinfunction "-_-") (pintype "passive"))
      (node (ref "B2") (pin "-") (pinfunction "-_-") (pintype "passive"))
      (node (ref "C10") (pin "2") (pinfunction "2_2") (pintype "passive"))
      (node (ref "C11") (pin "2") (pinfunction "2_2") (pintype "passive"))
      (node (ref "C13") (pin "2") (pinfunction "2_2") (pintype "passive"))
      (node (ref "C14") (pin "2") (pinfunction "2_2") (pintype "passive"))
      (node (ref "C15") (pin "2") (pinfunction "2_2") (pintype "passive"))
      (node (ref "C16") (pin "2") (pinfunction "2_2") (pintype "passive"))
      (node (ref "C17") (pin "2") (pinfunction "2_2") (pintype "passive"))
      (node (ref "C18") (pin "2") (pinfunction "2_2") (pintype "passive"))
      (node (ref "C19") (pin "2") (pinfunction "2_2") (pintype "passive"))
      (node (ref "C2") (pin "2") (pinfunction "2_2") (pintype "passive"))
      (node (ref "C20") (pin "2") (pinfunction "2_2") (pintype "passive"))
      (node (ref "C21") (pin "2") (pinfunction "2_2") (pintype "passive"))
      (node (ref "C22") (pin "2") (pinfunction "2_2") (pintype "passive"))
      (node (ref "C23") (pin "2") (pinfunction "2_2") (pintype "passive"))
      (node (ref "C24") (pin "2") (pinfunction "2_2") (pintype "passive"))
      (node (ref "C25") (pin "2") (pinfunction "2_2") (pintype "passive"))
      (node (ref "C26") (pin "2") (pinfunction "2_2") (pintype "passive"))
      (node (ref "C27") (pin "2") (pinfunction "2_2") (pintype "passive"))
      (node (ref "C28") (pin "2") (pinfunction "2_2") (pintype "passive"))
      (node (ref "C29") (pin "2") (pinfunction "2_2") (pintype "passive"))
      (node (ref "C3") (pin "2") (pinfunction "2_2") (pintype "passive"))
      (node (ref "C4") (pin "2") (pinfunction "2_2") (pintype "passive"))
      (node (ref "C5") (pin "1") (pinfunction "1_1") (pintype "passive"))
      (node (ref "C7") (pin "2") (pinfunction "2_2") (pintype "passive"))
      (node (ref "C8") (pin "2") (pinfunction "2_2") (pintype "passive"))
      (node (ref "C9") (pin "2") (pinfunction "2_2") (pintype "passive"))
      (node (ref "GND1") (pin "1") (pinfunction "1_1") (pintype "passive"))
      (node (ref "GND2") (pin "1") (pinfunction "1_1") (pintype "passive"))
      (node (ref "GND3") (pin "1") (pinfunction "1_1") (pintype "passive"))
      (node (ref "JP1") (pin "P$2") (pinfunction "2_P$2") (pintype "passive"))
      (node (ref "JP2") (pin "P$2") (pinfunction "2_P$2") (pintype "passive"))
      (node (ref "JP3") (pin "P$1") (pinfunction "1_P$1") (pintype "passive"))
      (node (ref "JP4") (pin "P$2") (pinfunction "2_P$2") (pintype "passive"))
      (node (ref "JP5") (pin "2") (pinfunction "GND_2") (pintype "passive"))
      (node (ref "JP5") (pin "3") (pinfunction "GND_3") (pintype "passive"))
      (node (ref "JP5") (pin "4") (pinfunction "GND_4") (pintype "passive"))
      (node (ref "JP5") (pin "5") (pinfunction "GND_5") (pintype "passive"))
      (node (ref "JP6") (pin "P$2") (pinfunction "2_P$2") (pintype "passive"))
      (node (ref "JP7") (pin "P$2") (pinfunction "2_P$2") (pintype "passive"))
      (node (ref "JP8") (pin "10") (pinfunction "10_10") (pintype "passive"))
      (node (ref "JP9") (pin "P$4") (pinfunction "4_P$4") (pintype "passive"))
      (node (ref "R12") (pin "1") (pinfunction "1_1") (pintype "passive"))
      (node (ref "R26") (pin "2") (pinfunction "2_2") (pintype "passive"))
      (node (ref "R3") (pin "1") (pinfunction "1_1") (pintype "passive"))
      (node (ref "R34") (pin "2") (pinfunction "2_2") (pintype "passive"))
      (node (ref "U1") (pin "3") (pinfunction "GND_3") (pintype "input"))
      (node (ref "U1") (pin "4") (pinfunction "GNDS_4") (pintype "input"))
      (node (ref "U10") (pin "3") (pinfunction "GND_3") (pintype "passive"))
      (node (ref "U12") (pin "GND.") (pinfunction "GND._GND.") (pintype "bidirectional"))
      (node (ref "U12") (pin "GND..") (pinfunction "GND.._GND..") (pintype "bidirectional"))
      (node (ref "U14") (pin "1") (pinfunction "~{OE}_1") (pintype "input"))
      (node (ref "U14") (pin "3") (pinfunction "GND_3") (pintype "passive"))
      (node (ref "U15") (pin "8") (pinfunction "GND_8") (pintype "passive"))
      (node (ref "U16") (pin "6") (pinfunction "GND_6") (pintype "bidirectional"))
      (node (ref "U17") (pin "P$2") (pinfunction "GND$1_P$2") (pintype "power_in"))
      (node (ref "U17") (pin "P$4") (pinfunction "GND$2_P$4") (pintype "power_in"))
      (node (ref "U17") (pin "P$5") (pinfunction "GND$3_P$5") (pintype "power_in"))
      (node (ref "U18") (pin "2") (pinfunction "GND_2") (pintype "power_in"))
      (node (ref "U19") (pin "3") (pinfunction "GND_3") (pintype "passive"))
      (node (ref "U2") (pin "2") (pinfunction "GND_2") (pintype "passive"))
      (node (ref "U2") (pin "6") (pinfunction "VIN-_6") (pintype "input"))
      (node (ref "U20") (pin "10") (pinfunction "GND_10") (pintype "bidirectional"))
      (node (ref "U20") (pin "11") (pinfunction "GND_11") (pintype "bidirectional"))
      (node (ref "U20") (pin "12") (pinfunction "GND_12") (pintype "bidirectional"))
      (node (ref "U20") (pin "13") (pinfunction "GND_13") (pintype "bidirectional"))
      (node (ref "U20") (pin "14") (pinfunction "GND_14") (pintype "bidirectional"))
      (node (ref "U20") (pin "15") (pinfunction "GND_15") (pintype "bidirectional"))
      (node (ref "U20") (pin "2") (pinfunction "GND_2") (pintype "bidirectional"))
      (node (ref "U20") (pin "7") (pinfunction "GND_7") (pintype "bidirectional"))
      (node (ref "U20") (pin "8") (pinfunction "GND_8") (pintype "bidirectional"))
      (node (ref "U20") (pin "9") (pinfunction "GND_9") (pintype "bidirectional"))
      (node (ref "U21") (pin "3") (pinfunction "GND_3") (pintype "power_in"))
      (node (ref "U22") (pin "2") (pinfunction "V-_2") (pintype "power_in"))
      (node (ref "U24") (pin "2") (pinfunction "GND_2") (pintype "passive"))
      (node (ref "U25") (pin "4") (pinfunction "GND_4") (pintype "passive"))
      (node (ref "U26") (pin "9") (pinfunction "GND_9") (pintype "passive"))
      (node (ref "U3") (pin "2") (pinfunction "V-_2") (pintype "passive"))
      (node (ref "U4") (pin "3") (pinfunction "GND_3") (pintype "input"))
      (node (ref "U4") (pin "4") (pinfunction "GNDS_4") (pintype "input"))
      (node (ref "U6") (pin "2") (pinfunction "GND_2") (pintype "passive"))
      (node (ref "U6") (pin "6") (pinfunction "VIN-_6") (pintype "input"))
      (node (ref "U7") (pin "3") (pinfunction "GND_3") (pintype "bidirectional"))
      (node (ref "U8") (pin "3") (pinfunction "GND_3") (pintype "passive"))
      (node (ref "U9") (pin "P$12") (pinfunction "GND_P$12") (pintype "bidirectional"))
      (node (ref "U9") (pin "P$19") (pinfunction "GND_P$19") (pintype "bidirectional"))
      (node (ref "U9") (pin "P$3") (pinfunction "GND_P$3") (pintype "bidirectional"))
      (node (ref "U9") (pin "P$8") (pinfunction "GND_P$8") (pintype "bidirectional"))
    )
    (net (code "49") (name "Net-(B1-+)") (class "Default")
      (node (ref "B1") (pin "+$1") (pinfunction "+_+$1") (pintype "passive"))
      (node (ref "B1") (pin "+$2") (pinfunction "+1_+$2") (pintype "passive"))
      (node (ref "U9") (pin "P$4") (pinfunction "VBACKUP_P$4") (pintype "bidirectional"))
    )
    (net (code "50") (name "Net-(B2-+)") (class "Default")
      (node (ref "B2") (pin "+$1") (pinfunction "+_+$1") (pintype "passive"))
      (node (ref "B2") (pin "+$2") (pinfunction "+1_+$2") (pintype "passive"))
      (node (ref "U20") (pin "16") (pinfunction "VBAT_16") (pintype "bidirectional"))
    )
    (net (code "51") (name "Net-(D1-C)") (class "Default")
      (node (ref "C13") (pin "1") (pinfunction "1_1") (pintype "passive"))
      (node (ref "D1") (pin "1") (pinfunction "C_1") (pintype "passive"))
      (node (ref "U12") (pin "5V") (pinfunction "5V_5V") (pintype "bidirectional"))
    )
    (net (code "52") (name "Net-(D3-PadA)") (class "Default")
      (node (ref "D3") (pin "A") (pinfunction "A_A") (pintype "passive"))
      (node (ref "R27") (pin "2") (pinfunction "2_2") (pintype "passive"))
    )
    (net (code "53") (name "Net-(JP1-1)") (class "Default")
      (node (ref "C1") (pin "1") (pinfunction "1_1") (pintype "passive"))
      (node (ref "JP1") (pin "P$1") (pinfunction "1_P$1") (pintype "passive"))
      (node (ref "R1") (pin "1") (pinfunction "1_1") (pintype "passive"))
      (node (ref "U3") (pin "4") (pinfunction "-IN_4") (pintype "input"))
    )
    (net (code "54") (name "Net-(JP3-2)") (class "Default")
      (node (ref "JP3") (pin "P$2") (pinfunction "2_P$2") (pintype "passive"))
      (node (ref "U7") (pin "9") (pinfunction "S2_9") (pintype "bidirectional"))
    )
    (net (code "55") (name "Net-(JP4-1)") (class "Default")
      (node (ref "JP4") (pin "P$1") (pinfunction "1_P$1") (pintype "passive"))
      (node (ref "U7") (pin "2") (pinfunction "S1_2") (pintype "bidirectional"))
    )
    (net (code "56") (name "Net-(JP5-SIG)") (class "Default")
      (node (ref "JP5") (pin "1") (pinfunction "SIG_1") (pintype "passive"))
      (node (ref "U9") (pin "P$11") (pinfunction "EX_ANT_P$11") (pintype "bidirectional"))
    )
    (net (code "57") (name "Net-(JP6-1)") (class "Default")
      (node (ref "C18") (pin "1") (pinfunction "1_1") (pintype "passive"))
      (node (ref "JP6") (pin "P$1") (pinfunction "1_P$1") (pintype "passive"))
      (node (ref "R29") (pin "1") (pinfunction "1_1") (pintype "passive"))
      (node (ref "U21") (pin "5") (pinfunction "IN_5") (pintype "input"))
      (node (ref "VBATT") (pin "1") (pinfunction "1_1") (pintype "passive"))
    )
    (net (code "58") (name "Net-(JP7-1)") (class "Default")
      (node (ref "JP7") (pin "P$1") (pinfunction "1_P$1") (pintype "passive"))
      (node (ref "Q7") (pin "3") (pinfunction "C_3") (pintype "passive"))
    )
    (net (code "59") (name "Net-(JP7-3)") (class "Default")
      (node (ref "JP7") (pin "P$3") (pinfunction "3_P$3") (pintype "passive"))
      (node (ref "U24") (pin "1") (pinfunction "VIN+_1") (pintype "input"))
    )
    (net (code "60") (name "Net-(JP7-4)") (class "Default")
      (node (ref "JP7") (pin "P$4") (pinfunction "4_P$4") (pintype "passive"))
      (node (ref "U24") (pin "6") (pinfunction "VIN-_6") (pintype "input"))
      (node (ref "U25") (pin "1") (pinfunction "NO1_1") (pintype "passive"))
      (node (ref "U25") (pin "5") (pinfunction "NO2_5") (pintype "passive"))
    )
    (net (code "61") (name "Net-(JP7-5)") (class "Default")
      (node (ref "JP7") (pin "P$5") (pinfunction "5_P$5") (pintype "passive"))
      (node (ref "U25") (pin "7") (pinfunction "IN1_7") (pintype "input"))
    )
    (net (code "62") (name "Net-(JP7-6)") (class "Default")
      (node (ref "JP7") (pin "P$6") (pinfunction "6_P$6") (pintype "passive"))
      (node (ref "U25") (pin "3") (pinfunction "IN2_3") (pintype "input"))
    )
    (net (code "63") (name "Net-(JP8-Pad7)") (class "Default")
      (node (ref "JP8") (pin "7") (pinfunction "7_7") (pintype "passive"))
      (node (ref "R25") (pin "2") (pinfunction "2_2") (pintype "passive"))
    )
    (net (code "64") (name "Net-(JP9-1)") (class "Default")
      (node (ref "JP9") (pin "P$1") (pinfunction "1_P$1") (pintype "passive"))
      (node (ref "Q8") (pin "3") (pinfunction "C_3") (pintype "passive"))
    )
    (net (code "65") (name "Net-(JP9-5)") (class "Default")
      (node (ref "JP9") (pin "P$5") (pinfunction "5_P$5") (pintype "passive"))
      (node (ref "R32") (pin "2") (pinfunction "2_2") (pintype "passive"))
    )
    (net (code "66") (name "Net-(Q3-B)") (class "Default")
      (node (ref "Q3") (pin "1") (pinfunction "B_1") (pintype "passive"))
      (node (ref "R23") (pin "2") (pinfunction "2_2") (pintype "passive"))
      (node (ref "R24") (pin "1") (pinfunction "1_1") (pintype "passive"))
    )
    (net (code "67") (name "Net-(Q3-C)") (class "Default")
      (node (ref "JP8") (pin "8") (pinfunction "8_8") (pintype "passive"))
      (node (ref "Q3") (pin "3") (pinfunction "C_3") (pintype "passive"))
    )
    (net (code "68") (name "Net-(Q4-B)") (class "Default")
      (node (ref "Q4") (pin "1") (pinfunction "B_1") (pintype "passive"))
      (node (ref "R18") (pin "2") (pinfunction "2_2") (pintype "passive"))
      (node (ref "R20") (pin "1") (pinfunction "1_1") (pintype "passive"))
    )
    (net (code "69") (name "Net-(Q5-B)") (class "Default")
      (node (ref "Q5") (pin "1") (pinfunction "B_1") (pintype "passive"))
      (node (ref "R17") (pin "2") (pinfunction "2_2") (pintype "passive"))
      (node (ref "R19") (pin "1") (pinfunction "1_1") (pintype "passive"))
    )
    (net (code "70") (name "Net-(Q6-B)") (class "Default")
      (node (ref "Q6") (pin "1") (pinfunction "B_1") (pintype "passive"))
      (node (ref "R21") (pin "2") (pinfunction "2_2") (pintype "passive"))
      (node (ref "R22") (pin "1") (pinfunction "1_1") (pintype "passive"))
    )
    (net (code "71") (name "Net-(Q6-C)") (class "Default")
      (node (ref "C11") (pin "1") (pinfunction "1_1") (pintype "passive"))
      (node (ref "Q6") (pin "3") (pinfunction "C_3") (pintype "passive"))
      (node (ref "U9") (pin "P$1") (pinfunction "VCC_P$1") (pintype "bidirectional"))
    )
    (net (code "72") (name "Net-(Q7-B)") (class "Default")
      (node (ref "Q7") (pin "1") (pinfunction "B_1") (pintype "passive"))
      (node (ref "R15") (pin "2") (pinfunction "2_2") (pintype "passive"))
      (node (ref "R16") (pin "1") (pinfunction "1_1") (pintype "passive"))
    )
    (net (code "73") (name "Net-(Q8-B)") (class "Default")
      (node (ref "Q8") (pin "1") (pinfunction "B_1") (pintype "passive"))
      (node (ref "R30") (pin "2") (pinfunction "2_2") (pintype "passive"))
      (node (ref "R31") (pin "1") (pinfunction "1_1") (pintype "passive"))
    )
    (net (code "74") (name "Net-(U1-NR)") (class "Default")
      (node (ref "C3") (pin "1") (pinfunction "1_1") (pintype "passive"))
      (node (ref "U1") (pin "1") (pinfunction "NR_1") (pintype "bidirectional"))
    )
    (net (code "75") (name "Net-(U1-OUTF)") (class "Default")
      (node (ref "+3VP*") (pin "1") (pinfunction "1_1") (pintype "passive"))
      (node (ref "C4") (pin "1") (pinfunction "1_1") (pintype "passive"))
      (node (ref "C5") (pin "2") (pinfunction "2_2") (pintype "passive"))
      (node (ref "R2") (pin "2") (pinfunction "2_2") (pintype "passive"))
      (node (ref "U1") (pin "6") (pinfunction "OUTS_6") (pintype "output"))
      (node (ref "U1") (pin "7") (pinfunction "OUTF_7") (pintype "output"))
      (node (ref "U2") (pin "5") (pinfunction "VDD_5") (pintype "power_in"))
      (node (ref "U3") (pin "5") (pinfunction "V+_5") (pintype "power_in"))
    )
    (net (code "76") (name "Net-(U2-VIN+)") (class "Default")
      (node (ref "C1") (pin "2") (pinfunction "2_2") (pintype "passive"))
      (node (ref "R1") (pin "2") (pinfunction "2_2") (pintype "passive"))
      (node (ref "U2") (pin "1") (pinfunction "VIN+_1") (pintype "input"))
      (node (ref "U3") (pin "1") (pinfunction "OUT_1") (pintype "output"))
      (node (ref "VPAR") (pin "1") (pinfunction "1_1") (pintype "passive"))
    )
    (net (code "77") (name "Net-(U3-+IN)") (class "Default")
      (node (ref "C2") (pin "1") (pinfunction "1_1") (pintype "passive"))
      (node (ref "R2") (pin "1") (pinfunction "1_1") (pintype "passive"))
      (node (ref "R3") (pin "2") (pinfunction "2_2") (pintype "passive"))
      (node (ref "U3") (pin "3") (pinfunction "+IN_3") (pintype "input"))
    )
    (net (code "78") (name "Net-(U4-NR)") (class "Default")
      (node (ref "C7") (pin "1") (pinfunction "1_1") (pintype "passive"))
      (node (ref "U4") (pin "1") (pinfunction "NR_1") (pintype "bidirectional"))
    )
    (net (code "79") (name "Net-(U4-OUTF)") (class "Default")
      (node (ref "+3VT*") (pin "1") (pinfunction "1_1") (pintype "passive"))
      (node (ref "C8") (pin "1") (pinfunction "1_1") (pintype "passive"))
      (node (ref "U4") (pin "6") (pinfunction "OUTS_6") (pintype "output"))
      (node (ref "U4") (pin "7") (pinfunction "OUTF_7") (pintype "output"))
      (node (ref "U6") (pin "5") (pinfunction "VDD_5") (pintype "power_in"))
    )
    (net (code "80") (name "Net-(U6-VIN+)") (class "Default")
      (node (ref "R33") (pin "1") (pinfunction "1_1") (pintype "passive"))
      (node (ref "U6") (pin "1") (pinfunction "VIN+_1") (pintype "input"))
    )
    (net (code "81") (name "Net-(U7-S3)") (class "Default")
      (node (ref "R12") (pin "2") (pinfunction "2_2") (pintype "passive"))
      (node (ref "U7") (pin "4") (pinfunction "S3_4") (pintype "bidirectional"))
    )
    (net (code "82") (name "Net-(U7-S4)") (class "Default")
      (node (ref "R34") (pin "1") (pinfunction "1_1") (pintype "passive"))
      (node (ref "U7") (pin "7") (pinfunction "S4_7") (pintype "bidirectional"))
    )
    (net (code "83") (name "Net-(U10-Y)") (class "Default")
      (node (ref "U10") (pin "4") (pinfunction "Y_4") (pintype "output"))
      (node (ref "U17") (pin "P$13") (pinfunction "MOSI_P$13") (pintype "input"))
    )
    (net (code "84") (name "Net-(U19-A)") (class "Default")
      (node (ref "R28") (pin "2") (pinfunction "2_2") (pintype "passive"))
      (node (ref "U19") (pin "2") (pinfunction "A_2") (pintype "input"))
      (node (ref "U20") (pin "5") (pinfunction "INT/SQW_5") (pintype "bidirectional"))
    )
    (net (code "85") (name "Net-(U19-VCC)") (class "Default")
      (node (ref "ALARM") (pin "1") (pinfunction "1_1") (pintype "passive"))
      (node (ref "R28") (pin "1") (pinfunction "1_1") (pintype "passive"))
      (node (ref "R29") (pin "2") (pinfunction "2_2") (pintype "passive"))
      (node (ref "U19") (pin "5") (pinfunction "VCC_5") (pintype "power_in"))
    )
    (net (code "86") (name "Net-(U19-Y)") (class "Default")
      (node (ref "D2") (pin "A") (pinfunction "A_A") (pintype "passive"))
      (node (ref "U19") (pin "4") (pinfunction "Y_4") (pintype "output"))
    )
    (net (code "87") (name "Net-(U21-~{SHDN})") (class "Default")
      (node (ref "C22") (pin "1") (pinfunction "1_1") (pintype "passive"))
      (node (ref "D2") (pin "C") (pinfunction "C_C") (pintype "passive"))
      (node (ref "D3") (pin "C") (pinfunction "C_C") (pintype "passive"))
      (node (ref "R26") (pin "1") (pinfunction "1_1") (pintype "passive"))
      (node (ref "SHTDN") (pin "1") (pinfunction "1_1") (pintype "passive"))
      (node (ref "U21") (pin "4") (pinfunction "~{SHDN}_4") (pintype "input"))
    )
    (net (code "88") (name "Net-(U22-+INA)") (class "Default")
      (node (ref "C27") (pin "1") (pinfunction "1_1") (pintype "passive"))
      (node (ref "R6") (pin "1") (pinfunction "1_1") (pintype "passive"))
      (node (ref "U22") (pin "1") (pinfunction "+INA_1") (pintype "input"))
      (node (ref "U22") (pin "3") (pinfunction "+INB_3") (pintype "input"))
      (node (ref "U7") (pin "8") (pinfunction "COM_8") (pintype "bidirectional"))
    )
    (net (code "89") (name "Net-(U22--INA)") (class "Default")
      (node (ref "U22") (pin "7") (pinfunction "OUTA_7") (pintype "output"))
      (node (ref "U22") (pin "8") (pinfunction "-INA_8") (pintype "input"))
      (node (ref "U23") (pin "4") (pinfunction "GND_4") (pintype "passive"))
    )
    (net (code "90") (name "Net-(U22--INB)") (class "Default")
      (node (ref "R33") (pin "2") (pinfunction "2_2") (pintype "passive"))
      (node (ref "U22") (pin "4") (pinfunction "-INB_4") (pintype "input"))
      (node (ref "U22") (pin "5") (pinfunction "OUTB_5") (pintype "output"))
    )
    (net (code "91") (name "Net-(U23-VOUT)") (class "Default")
      (node (ref "R4") (pin "1") (pinfunction "1_1") (pintype "passive"))
      (node (ref "R6") (pin "2") (pinfunction "2_2") (pintype "passive"))
      (node (ref "U23") (pin "6") (pinfunction "VOUT_6") (pintype "passive"))
    )
    (net (code "92") (name "Net-(U25-COM1)") (class "Default")
      (node (ref "R13") (pin "2") (pinfunction "2_2") (pintype "passive"))
      (node (ref "U25") (pin "2") (pinfunction "COM1_2") (pintype "passive"))
    )
    (net (code "93") (name "Net-(U25-COM2)") (class "Default")
      (node (ref "R14") (pin "2") (pinfunction "2_2") (pintype "passive"))
      (node (ref "U25") (pin "6") (pinfunction "COM2_6") (pintype "passive"))
    )
    (net (code "94") (name "unconnected-(JP8-Pad2)") (class "Default")
      (node (ref "JP8") (pin "2") (pinfunction "2_2") (pintype "passive"))
    )
    (net (code "95") (name "unconnected-(JP8-Pad3)") (class "Default")
      (node (ref "JP8") (pin "3") (pinfunction "3_3") (pintype "passive"))
    )
    (net (code "96") (name "unconnected-(JP8-Pad4)") (class "Default")
      (node (ref "JP8") (pin "4") (pinfunction "4_4") (pintype "passive"))
    )
    (net (code "97") (name "unconnected-(JP8-Pad5)") (class "Default")
      (node (ref "JP8") (pin "5") (pinfunction "5_5") (pintype "passive"))
    )
    (net (code "98") (name "unconnected-(JP8-Pad9)") (class "Default")
      (node (ref "JP8") (pin "9") (pinfunction "9_9") (pintype "passive"))
    )
    (net (code "99") (name "unconnected-(U8-NC-Pad1)") (class "Default")
      (node (ref "U8") (pin "1") (pinfunction "NC_1") (pintype "no_connect"))
    )
    (net (code "100") (name "unconnected-(U9-1PPS-PadP$13)") (class "Default")
      (node (ref "U9") (pin "P$13") (pinfunction "1PPS_P$13") (pintype "bidirectional"))
    )
    (net (code "101") (name "unconnected-(U9-3D-FIX-PadP$5)") (class "Default")
      (node (ref "U9") (pin "P$5") (pinfunction "3D-FIX_P$5") (pintype "bidirectional"))
    )
    (net (code "102") (name "unconnected-(U9-NC-PadP$6)") (class "Default")
      (node (ref "U9") (pin "P$6") (pinfunction "NC_P$6") (pintype "bidirectional"))
    )
    (net (code "103") (name "unconnected-(U9-NC-PadP$7)") (class "Default")
      (node (ref "U9") (pin "P$7") (pinfunction "NC_P$7") (pintype "bidirectional"))
    )
    (net (code "104") (name "unconnected-(U9-NC-PadP$15)") (class "Default")
      (node (ref "U9") (pin "P$15") (pinfunction "NC_P$15") (pintype "bidirectional"))
    )
    (net (code "105") (name "unconnected-(U9-NC-PadP$16)") (class "Default")
      (node (ref "U9") (pin "P$16") (pinfunction "NC_P$16") (pintype "bidirectional"))
    )
    (net (code "106") (name "unconnected-(U9-NC-PadP$17)") (class "Default")
      (node (ref "U9") (pin "P$17") (pinfunction "NC_P$17") (pintype "bidirectional"))
    )
    (net (code "107") (name "unconnected-(U9-NC-PadP$18)") (class "Default")
      (node (ref "U9") (pin "P$18") (pinfunction "NC_P$18") (pintype "bidirectional"))
    )
    (net (code "108") (name "unconnected-(U9-NC-PadP$20)") (class "Default")
      (node (ref "U9") (pin "P$20") (pinfunction "NC_P$20") (pintype "bidirectional"))
    )
    (net (code "109") (name "unconnected-(U9-NRESET-PadP$2)") (class "Default")
      (node (ref "U9") (pin "P$2") (pinfunction "NRESET_P$2") (pintype "bidirectional"))
    )
    (net (code "110") (name "unconnected-(U9-RTCM-PadP$14)") (class "Default")
      (node (ref "U9") (pin "P$14") (pinfunction "RTCM_P$14") (pintype "bidirectional"))
    )
    (net (code "111") (name "unconnected-(U12-(N{slash}C)-PadN{slash}C)") (class "Default")
      (node (ref "U12") (pin "N/C") (pinfunction "(N/C)_N/C") (pintype "bidirectional"))
    )
    (net (code "112") (name "unconnected-(U12-+5V.-Pad5V.)") (class "Default")
      (node (ref "U12") (pin "5V.") (pinfunction "+5V._5V.") (pintype "bidirectional"))
    )
    (net (code "113") (name "unconnected-(U12-+5V..-Pad5V..)") (class "Default")
      (node (ref "U12") (pin "5V..") (pinfunction "+5V.._5V..") (pintype "bidirectional"))
    )
    (net (code "114") (name "unconnected-(U12-0(RX)-Pad0)") (class "Default")
      (node (ref "U12") (pin "0") (pinfunction "0(RX)_0") (pintype "bidirectional"))
    )
    (net (code "115") (name "unconnected-(U12-1(TX)-Pad1)") (class "Default")
      (node (ref "U12") (pin "1") (pinfunction "1(TX)_1") (pintype "bidirectional"))
    )
    (net (code "116") (name "unconnected-(U12-IOREF-PadI{slash}OREF)") (class "Default")
      (node (ref "U12") (pin "I/OREF") (pinfunction "IOREF_I/OREF") (pintype "bidirectional"))
    )
    (net (code "117") (name "unconnected-(U12-Pad+5V_)") (class "Default")
      (node (ref "U12") (pin "+5V_") (pinfunction "+5V__+5V_") (pintype "bidirectional"))
    )
    (net (code "118") (name "unconnected-(U12-Pad3.3V)") (class "Default")
      (node (ref "U12") (pin "3.3V") (pinfunction "3.3V_3.3V") (pintype "bidirectional"))
    )
    (net (code "119") (name "unconnected-(U12-Pad5)") (class "Default")
      (node (ref "U12") (pin "5") (pinfunction "5_5") (pintype "bidirectional"))
    )
    (net (code "120") (name "unconnected-(U12-Pad7)") (class "Default")
      (node (ref "U12") (pin "7") (pinfunction "7_7") (pintype "bidirectional"))
    )
    (net (code "121") (name "unconnected-(U12-Pad10)") (class "Default")
      (node (ref "U12") (pin "10") (pinfunction "10_10") (pintype "bidirectional"))
    )
    (net (code "122") (name "unconnected-(U12-Pad22)") (class "Default")
      (node (ref "U12") (pin "22") (pinfunction "22_22") (pintype "bidirectional"))
    )
    (net (code "123") (name "unconnected-(U12-Pad23)") (class "Default")
      (node (ref "U12") (pin "23") (pinfunction "23_23") (pintype "bidirectional"))
    )
    (net (code "124") (name "unconnected-(U12-Pad25)") (class "Default")
      (node (ref "U12") (pin "25") (pinfunction "25_25") (pintype "bidirectional"))
    )
    (net (code "125") (name "unconnected-(U12-Pad27)") (class "Default")
      (node (ref "U12") (pin "27") (pinfunction "27_27") (pintype "bidirectional"))
    )
    (net (code "126") (name "unconnected-(U12-Pad29)") (class "Default")
      (node (ref "U12") (pin "29") (pinfunction "29_29") (pintype "bidirectional"))
    )
    (net (code "127") (name "unconnected-(U12-Pad30)") (class "Default")
      (node (ref "U12") (pin "30") (pinfunction "30_30") (pintype "bidirectional"))
    )
    (net (code "128") (name "unconnected-(U12-Pad31)") (class "Default")
      (node (ref "U12") (pin "31") (pinfunction "31_31") (pintype "bidirectional"))
    )
    (net (code "129") (name "unconnected-(U12-Pad33)") (class "Default")
      (node (ref "U12") (pin "33") (pinfunction "33_33") (pintype "bidirectional"))
    )
    (net (code "130") (name "unconnected-(U12-Pad34)") (class "Default")
      (node (ref "U12") (pin "34") (pinfunction "34_34") (pintype "bidirectional"))
    )
    (net (code "131") (name "unconnected-(U12-Pad35)") (class "Default")
      (node (ref "U12") (pin "35") (pinfunction "35_35") (pintype "bidirectional"))
    )
    (net (code "132") (name "unconnected-(U12-Pad36)") (class "Default")
      (node (ref "U12") (pin "36") (pinfunction "36_36") (pintype "bidirectional"))
    )
    (net (code "133") (name "unconnected-(U12-Pad37)") (class "Default")
      (node (ref "U12") (pin "37") (pinfunction "37_37") (pintype "bidirectional"))
    )
    (net (code "134") (name "unconnected-(U12-Pad38)") (class "Default")
      (node (ref "U12") (pin "38") (pinfunction "38_38") (pintype "bidirectional"))
    )
    (net (code "135") (name "unconnected-(U12-Pad39)") (class "Default")
      (node (ref "U12") (pin "39") (pinfunction "39_39") (pintype "bidirectional"))
    )
    (net (code "136") (name "unconnected-(U12-Pad40)") (class "Default")
      (node (ref "U12") (pin "40") (pinfunction "40_40") (pintype "bidirectional"))
    )
    (net (code "137") (name "unconnected-(U12-Pad41)") (class "Default")
      (node (ref "U12") (pin "41") (pinfunction "41_41") (pintype "bidirectional"))
    )
    (net (code "138") (name "unconnected-(U12-Pad42)") (class "Default")
      (node (ref "U12") (pin "42") (pinfunction "42_42") (pintype "bidirectional"))
    )
    (net (code "139") (name "unconnected-(U12-Pad43)") (class "Default")
      (node (ref "U12") (pin "43") (pinfunction "43_43") (pintype "bidirectional"))
    )
    (net (code "140") (name "unconnected-(U12-Pad44)") (class "Default")
      (node (ref "U12") (pin "44") (pinfunction "44_44") (pintype "bidirectional"))
    )
    (net (code "141") (name "unconnected-(U12-Pad45)") (class "Default")
      (node (ref "U12") (pin "45") (pinfunction "45_45") (pintype "bidirectional"))
    )
    (net (code "142") (name "unconnected-(U12-Pad46)") (class "Default")
      (node (ref "U12") (pin "46") (pinfunction "46_46") (pintype "bidirectional"))
    )
    (net (code "143") (name "unconnected-(U12-Pad47)") (class "Default")
      (node (ref "U12") (pin "47") (pinfunction "47_47") (pintype "bidirectional"))
    )
    (net (code "144") (name "unconnected-(U12-Pad48)") (class "Default")
      (node (ref "U12") (pin "48") (pinfunction "48_48") (pintype "bidirectional"))
    )
    (net (code "145") (name "unconnected-(U12-Pad49)") (class "Default")
      (node (ref "U12") (pin "49") (pinfunction "49_49") (pintype "bidirectional"))
    )
    (net (code "146") (name "unconnected-(U12-Pad50)") (class "Default")
      (node (ref "U12") (pin "50") (pinfunction "50_50") (pintype "bidirectional"))
    )
    (net (code "147") (name "unconnected-(U12-Pad51)") (class "Default")
      (node (ref "U12") (pin "51") (pinfunction "51_51") (pintype "bidirectional"))
    )
    (net (code "148") (name "unconnected-(U12-Pad52)") (class "Default")
      (node (ref "U12") (pin "52") (pinfunction "52_52") (pintype "bidirectional"))
    )
    (net (code "149") (name "unconnected-(U12-Pad53)") (class "Default")
      (node (ref "U12") (pin "53") (pinfunction "53_53") (pintype "bidirectional"))
    )
    (net (code "150") (name "unconnected-(U12-PadA1)") (class "Default")
      (node (ref "U12") (pin "A1") (pinfunction "A1_A1") (pintype "bidirectional"))
    )
    (net (code "151") (name "unconnected-(U12-PadA3)") (class "Default")
      (node (ref "U12") (pin "A3") (pinfunction "A3_A3") (pintype "bidirectional"))
    )
    (net (code "152") (name "unconnected-(U12-PadA4)") (class "Default")
      (node (ref "U12") (pin "A4") (pinfunction "A4_A4") (pintype "bidirectional"))
    )
    (net (code "153") (name "unconnected-(U12-PadA6)") (class "Default")
      (node (ref "U12") (pin "A6") (pinfunction "A6_A6") (pintype "bidirectional"))
    )
    (net (code "154") (name "unconnected-(U12-PadA7)") (class "Default")
      (node (ref "U12") (pin "A7") (pinfunction "A7_A7") (pintype "bidirectional"))
    )
    (net (code "155") (name "unconnected-(U12-PadA9)") (class "Default")
      (node (ref "U12") (pin "A9") (pinfunction "A9_A9") (pintype "bidirectional"))
    )
    (net (code "156") (name "unconnected-(U12-PadA10)") (class "Default")
      (node (ref "U12") (pin "A10") (pinfunction "A10_A10") (pintype "bidirectional"))
    )
    (net (code "157") (name "unconnected-(U12-PadA11)") (class "Default")
      (node (ref "U12") (pin "A11") (pinfunction "A11_A11") (pintype "bidirectional"))
    )
    (net (code "158") (name "unconnected-(U12-PadA12)") (class "Default")
      (node (ref "U12") (pin "A12") (pinfunction "A12_A12") (pintype "bidirectional"))
    )
    (net (code "159") (name "unconnected-(U12-PadA13)") (class "Default")
      (node (ref "U12") (pin "A13") (pinfunction "A13_A13") (pintype "bidirectional"))
    )
    (net (code "160") (name "unconnected-(U12-PadA14)") (class "Default")
      (node (ref "U12") (pin "A14") (pinfunction "A14_A14") (pintype "bidirectional"))
    )
    (net (code "161") (name "unconnected-(U12-PadA15)") (class "Default")
      (node (ref "U12") (pin "A15") (pinfunction "A15_A15") (pintype "bidirectional"))
    )
    (net (code "162") (name "unconnected-(U12-PadAREF)") (class "Default")
      (node (ref "U12") (pin "AREF") (pinfunction "AREF_AREF") (pintype "bidirectional"))
    )
    (net (code "163") (name "unconnected-(U12-PadGND)") (class "Default")
      (node (ref "U12") (pin "GND") (pinfunction "GND_GND") (pintype "bidirectional"))
    )
    (net (code "164") (name "unconnected-(U12-PadGND...)") (class "Default")
      (node (ref "U12") (pin "GND...") (pinfunction "GND..._GND...") (pintype "bidirectional"))
    )
    (net (code "165") (name "unconnected-(U12-PadGND....)") (class "Default")
      (node (ref "U12") (pin "GND....") (pinfunction "GND...._GND....") (pintype "bidirectional"))
    )
    (net (code "166") (name "unconnected-(U12-PadGND__)") (class "Default")
      (node (ref "U12") (pin "GND__") (pinfunction "GND___GND__") (pintype "bidirectional"))
    )
    (net (code "167") (name "unconnected-(U12-PadRESET)") (class "Default")
      (node (ref "U12") (pin "RESET") (pinfunction "RESET_RESET") (pintype "bidirectional"))
    )
    (net (code "168") (name "unconnected-(U12-PadRESET.)") (class "Default")
      (node (ref "U12") (pin "RESET.") (pinfunction "RESET._RESET.") (pintype "bidirectional"))
    )
    (net (code "169") (name "unconnected-(U12-PadSCL1)") (class "Default")
      (node (ref "U12") (pin "SCL1") (pinfunction "SCL1_SCL1") (pintype "bidirectional"))
    )
    (net (code "170") (name "unconnected-(U12-PadSDA1)") (class "Default")
      (node (ref "U12") (pin "SDA1") (pinfunction "SDA1_SDA1") (pintype "bidirectional"))
    )
    (net (code "171") (name "unconnected-(U12-PadVIN)") (class "Default")
      (node (ref "U12") (pin "VIN") (pinfunction "VIN_VIN") (pintype "bidirectional"))
    )
    (net (code "172") (name "unconnected-(U15-6A-Pad14)") (class "Default")
      (node (ref "U15") (pin "14") (pinfunction "6A_14") (pintype "input"))
    )
    (net (code "173") (name "unconnected-(U15-6Y-Pad15)") (class "Default")
      (node (ref "U15") (pin "15") (pinfunction "6Y_15") (pintype "output"))
    )
    (net (code "174") (name "unconnected-(U15-NC-Pad16)") (class "Default")
      (node (ref "U15") (pin "16") (pinfunction "NC_16") (pintype "no_connect"))
    )
    (net (code "175") (name "unconnected-(U15-NC_2-Pad13)") (class "Default")
      (node (ref "U15") (pin "13") (pinfunction "NC_2_13") (pintype "no_connect"))
    )
    (net (code "176") (name "unconnected-(U16-NC-Pad1)") (class "Default")
      (node (ref "U16") (pin "1") (pinfunction "NC_1") (pintype "bidirectional"))
    )
    (net (code "177") (name "unconnected-(U16-PadCD1)") (class "Default")
      (node (ref "U16") (pin "CD1") (pinfunction "CD1_CD1") (pintype "bidirectional"))
    )
    (net (code "178") (name "unconnected-(U16-PadCD2)") (class "Default")
      (node (ref "U16") (pin "CD2") (pinfunction "CD2_CD2") (pintype "bidirectional"))
    )
    (net (code "179") (name "unconnected-(U16-RSV-Pad8)") (class "Default")
      (node (ref "U16") (pin "8") (pinfunction "RSV_8") (pintype "bidirectional"))
    )
    (net (code "180") (name "unconnected-(U16-SHIELD-PadGND1)") (class "Default")
      (node (ref "U16") (pin "GND1") (pinfunction "SHIELD_GND1") (pintype "bidirectional"))
    )
    (net (code "181") (name "unconnected-(U16-SHIELD-PadGND3)") (class "Default")
      (node (ref "U16") (pin "GND3") (pinfunction "SHIELD_GND3") (pintype "bidirectional"))
    )
    (net (code "182") (name "unconnected-(U17-INT1-PadP$8)") (class "Default")
      (node (ref "U17") (pin "P$8") (pinfunction "INT1_P$8") (pintype "output"))
    )
    (net (code "183") (name "unconnected-(U17-INT2-PadP$9)") (class "Default")
      (node (ref "U17") (pin "P$9") (pinfunction "INT2_P$9") (pintype "output"))
    )
    (net (code "184") (name "unconnected-(U17-NC-PadP$10)") (class "Default")
      (node (ref "U17") (pin "P$10") (pinfunction "NC_P$10") (pintype "bidirectional"))
    )
    (net (code "185") (name "unconnected-(U17-RESERVED$1-PadP$3)") (class "Default")
      (node (ref "U17") (pin "P$3") (pinfunction "RESERVED$1_P$3") (pintype "bidirectional"))
    )
    (net (code "186") (name "unconnected-(U17-RESERVED$2-PadP$11)") (class "Default")
      (node (ref "U17") (pin "P$11") (pinfunction "RESERVED$2_P$11") (pintype "bidirectional"))
    )
    (net (code "187") (name "unconnected-(U18-NC{slash}FB-Pad4)") (class "Default")
      (node (ref "U18") (pin "4") (pinfunction "NC/FB_4") (pintype "passive"))
    )
    (net (code "188") (name "unconnected-(U19-NC-Pad1)") (class "Default")
      (node (ref "U19") (pin "1") (pinfunction "NC_1") (pintype "no_connect"))
    )
    (net (code "189") (name "unconnected-(U20-32KHZ-Pad3)") (class "Default")
      (node (ref "U20") (pin "3") (pinfunction "32KHZ_3") (pintype "bidirectional"))
    )
    (net (code "190") (name "unconnected-(U20-RST-Pad6)") (class "Default")
      (node (ref "U20") (pin "6") (pinfunction "RST_6") (pintype "bidirectional"))
    )
  )
)
